# SteppyMk2.net
KiCad netlist of a schematic drawn in EAGLE
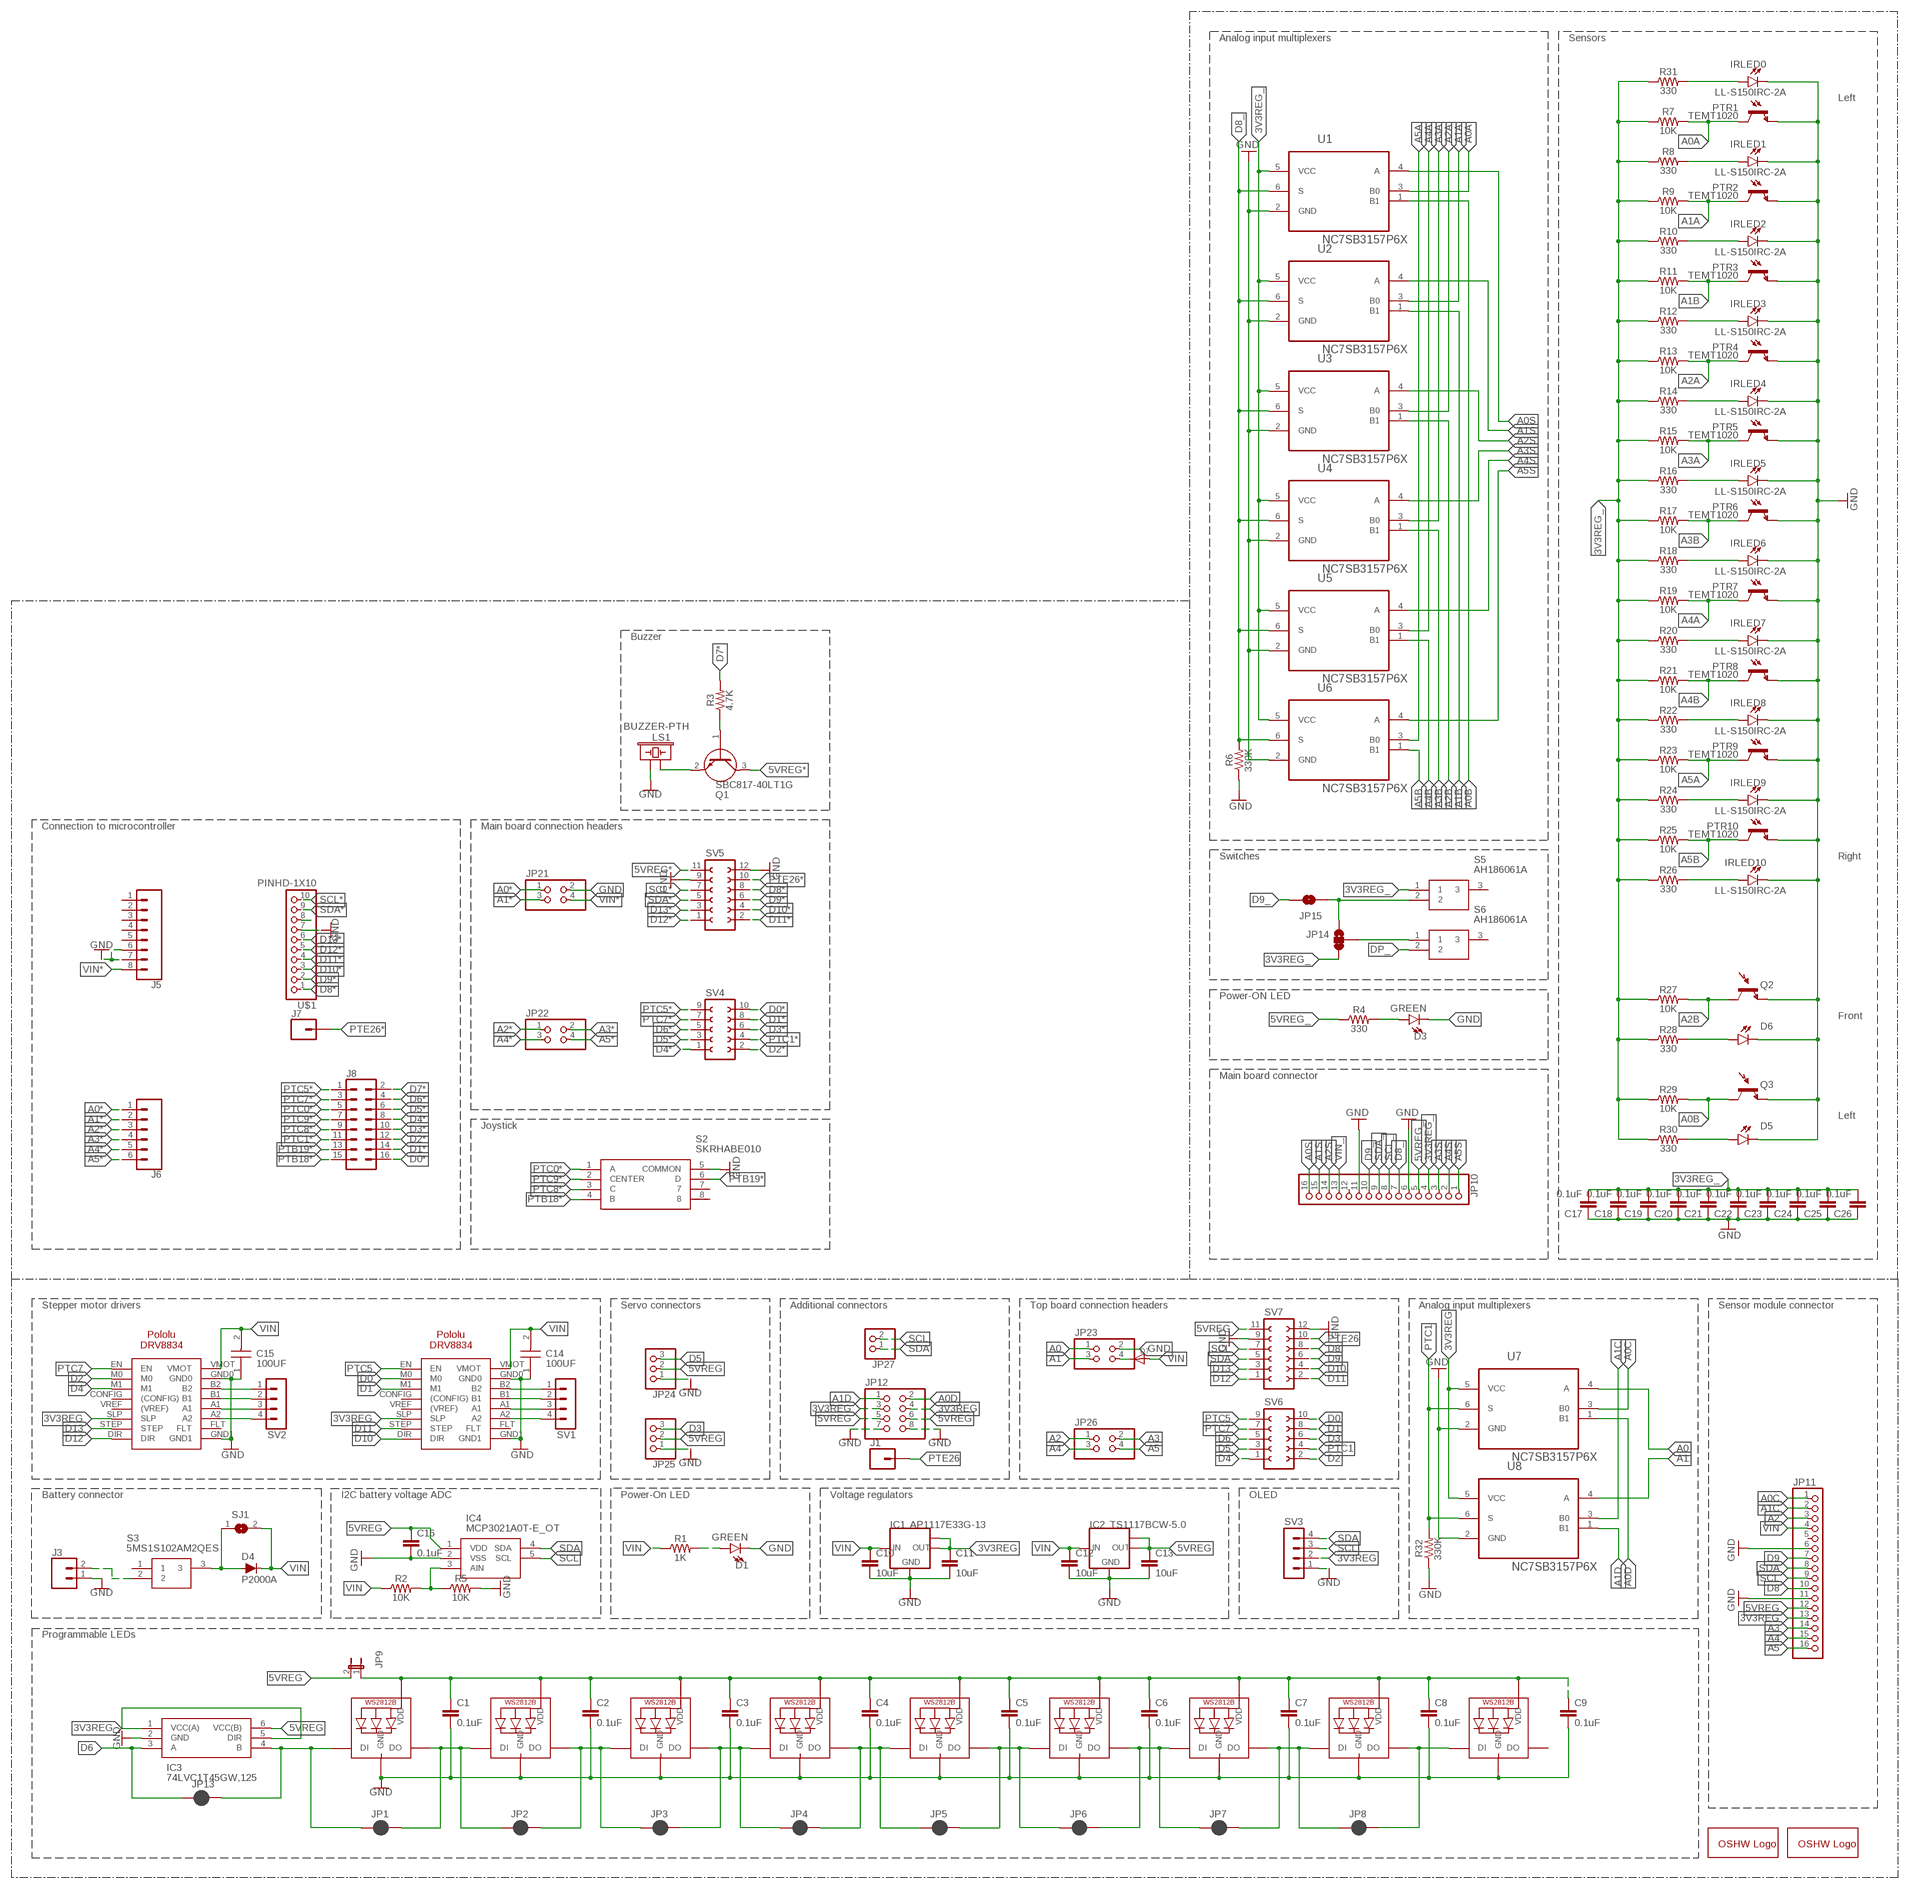
[diagram p0: schematic, sheet 1]

(export (version "E")
  (design (tool "Eeschema 10.0.6"))
  (components
    (comp (ref "C1")
      (value "0.1uF")
      (footprint "eagle-import:0603")
      (libsource (lib "eagle-import") (part "0.1UF-0603-25V-5%"))
    )
    (comp (ref "C2")
      (value "0.1uF")
      (footprint "eagle-import:0603")
      (libsource (lib "eagle-import") (part "0.1UF-0603-25V-5%"))
    )
    (comp (ref "C3")
      (value "0.1uF")
      (footprint "eagle-import:0603")
      (libsource (lib "eagle-import") (part "0.1UF-0603-25V-5%"))
    )
    (comp (ref "C4")
      (value "0.1uF")
      (footprint "eagle-import:0603")
      (libsource (lib "eagle-import") (part "0.1UF-0603-25V-5%"))
    )
    (comp (ref "C5")
      (value "0.1uF")
      (footprint "eagle-import:0603")
      (libsource (lib "eagle-import") (part "0.1UF-0603-25V-5%"))
    )
    (comp (ref "C6")
      (value "0.1uF")
      (footprint "eagle-import:0603")
      (libsource (lib "eagle-import") (part "0.1UF-0603-25V-5%"))
    )
    (comp (ref "C7")
      (value "0.1uF")
      (footprint "eagle-import:0603")
      (libsource (lib "eagle-import") (part "0.1UF-0603-25V-5%"))
    )
    (comp (ref "C8")
      (value "0.1uF")
      (footprint "eagle-import:0603")
      (libsource (lib "eagle-import") (part "0.1UF-0603-25V-5%"))
    )
    (comp (ref "C9")
      (value "0.1uF")
      (footprint "eagle-import:0603")
      (libsource (lib "eagle-import") (part "0.1UF-0603-25V-5%"))
    )
    (comp (ref "C10")
      (value "10uF")
      (footprint "eagle-import:0805")
      (libsource (lib "eagle-import") (part "10UF-0805-10V-10%"))
    )
    (comp (ref "C11")
      (value "10uF")
      (footprint "eagle-import:0805")
      (libsource (lib "eagle-import") (part "10UF-0805-10V-10%"))
    )
    (comp (ref "C12")
      (value "10uF")
      (footprint "eagle-import:0805")
      (libsource (lib "eagle-import") (part "10UF-0805-10V-10%"))
    )
    (comp (ref "C13")
      (value "10uF")
      (footprint "eagle-import:0805")
      (libsource (lib "eagle-import") (part "10UF-0805-10V-10%"))
    )
    (comp (ref "C14")
      (value "100UF")
      (footprint "eagle-import:CAPM7058X610N")
      (fields
        (field (name "MANUFACTURER_PART_NUMBER") "EEEFK1C101P")
        (field (name "RS_PART_NUMBER") "5370433P")
      )
      (libsource (lib "eagle-import") (part "EEEFK1C101P"))
    )
    (comp (ref "C15")
      (value "100UF")
      (footprint "eagle-import:CAPM7058X610N")
      (fields
        (field (name "MANUFACTURER_PART_NUMBER") "EEEFK1C101P")
        (field (name "RS_PART_NUMBER") "5370433P")
      )
      (libsource (lib "eagle-import") (part "EEEFK1C101P"))
    )
    (comp (ref "C16")
      (value "0.1uF")
      (footprint "eagle-import:0603")
      (libsource (lib "eagle-import") (part "0.1UF-0603-25V-5%"))
    )
    (comp (ref "C17")
      (value "0.1uF")
      (footprint "eagle-import:0603")
      (libsource (lib "eagle-import") (part "0.1UF-0603-25V-5%"))
    )
    (comp (ref "C18")
      (value "0.1uF")
      (footprint "eagle-import:0603")
      (libsource (lib "eagle-import") (part "0.1UF-0603-25V-5%"))
    )
    (comp (ref "C19")
      (value "0.1uF")
      (footprint "eagle-import:0603")
      (libsource (lib "eagle-import") (part "0.1UF-0603-25V-5%"))
    )
    (comp (ref "C20")
      (value "0.1uF")
      (footprint "eagle-import:0603")
      (libsource (lib "eagle-import") (part "0.1UF-0603-25V-5%"))
    )
    (comp (ref "C21")
      (value "0.1uF")
      (footprint "eagle-import:0603")
      (libsource (lib "eagle-import") (part "0.1UF-0603-25V-5%"))
    )
    (comp (ref "C22")
      (value "0.1uF")
      (footprint "eagle-import:0603")
      (libsource (lib "eagle-import") (part "0.1UF-0603-25V-5%"))
    )
    (comp (ref "C23")
      (value "0.1uF")
      (footprint "eagle-import:0603")
      (libsource (lib "eagle-import") (part "0.1UF-0603-25V-5%"))
    )
    (comp (ref "C24")
      (value "0.1uF")
      (footprint "eagle-import:0603")
      (libsource (lib "eagle-import") (part "0.1UF-0603-25V-5%"))
    )
    (comp (ref "C25")
      (value "0.1uF")
      (footprint "eagle-import:0603")
      (libsource (lib "eagle-import") (part "0.1UF-0603-25V-5%"))
    )
    (comp (ref "C26")
      (value "0.1uF")
      (footprint "eagle-import:0603")
      (libsource (lib "eagle-import") (part "0.1UF-0603-25V-5%"))
    )
    (comp (ref "CONLEFT")
      (value "POLOLU-DRV8825")
      (footprint "eagle-import:POLOLU-DRV8825")
      (libsource (lib "eagle-import") (part "POLOLU-DRV8825"))
    )
    (comp (ref "D1")
      (value "GREEN")
      (footprint "eagle-import:LED-1206")
      (libsource (lib "eagle-import") (part "LED-GREEN1206"))
    )
    (comp (ref "D3")
      (value "GREEN")
      (footprint "eagle-import:LED-1206")
      (libsource (lib "eagle-import") (part "LED-GREEN1206"))
    )
    (comp (ref "D4")
      (value "P2000A")
      (footprint "eagle-import:DIODE-1N4001")
      (libsource (lib "eagle-import") (part "DIODE-PTH"))
    )
    (comp (ref "D5")
      (value "LED-IRSIDE_EMITTER")
      (footprint "eagle-import:LTE-302")
      (libsource (lib "eagle-import") (part "LED-IRSIDE_EMITTER"))
    )
    (comp (ref "D6")
      (value "LED-IRSIDE_EMITTER")
      (footprint "eagle-import:LTE-302")
      (libsource (lib "eagle-import") (part "LED-IRSIDE_EMITTER"))
    )
    (comp (ref "D7")
      (value "DIODESMA")
      (footprint "eagle-import:SMADIODE")
      (libsource (lib "eagle-import") (part "DIODESMA"))
    )
    (comp (ref "GOLD_ORB_SM1")
      (value "OSHWLOGOLOGO8MM")
      (footprint "eagle-import:OSHW_8MM")
      (libsource (lib "eagle-import") (part "OSHWLOGOLOGO8MM"))
    )
    (comp (ref "GOLD_ORB_SM2")
      (value "OSHWLOGOLOGO5MM")
      (footprint "eagle-import:OSHW_5MM")
      (libsource (lib "eagle-import") (part "OSHWLOGOLOGO5MM"))
    )
    (comp (ref "IC1")
      (value "AP1117E33G-13")
      (footprint "eagle-import:SOT223")
      (libsource (lib "eagle-import") (part "LM1117IMPX-3.3"))
    )
    (comp (ref "IC2")
      (value "TS1117BCW-5.0")
      (footprint "eagle-import:SOT223")
      (libsource (lib "eagle-import") (part "LM1117IMPX-5.0"))
    )
    (comp (ref "IC3")
      (value "74LVC1T45GW,125")
      (footprint "eagle-import:SOT65P210X110-6N")
      (fields
        (field (name "MOUSER_PART_NUMBER") "771-74LVC1T45GW125")
        (field (name "RS_PART_NUMBER") "8168791P")
      )
      (libsource (lib "eagle-import") (part "74LVC1T45GW,125"))
    )
    (comp (ref "IC4")
      (value "MCP3021A0T-E_OT")
      (footprint "eagle-import:SOT95P280X145-5N")
      (fields
        (field (name "MANUFACTURER_PART_NUMBER") "MCP3021A0T-E/OT")
        (field (name "MOUSER_PART_NUMBER") "579-MCP3021A0T-E/OT")
      )
      (libsource (lib "eagle-import") (part "MCP3021A0T-E_OT"))
    )
    (comp (ref "IRLED0")
      (value "LL-S150IRC-2A")
      (footprint "eagle-import:LEDC3215X130N")
      (fields
        (field (name "MANUFACTURER_PART_NUMBER") "PT15-21C/TR8")
        (field (name "MOUSER_PART_NUMBER") "638-PT1521CTR8")
      )
      (libsource (lib "eagle-import") (part "PT15-21C_TR8"))
    )
    (comp (ref "IRLED1")
      (value "LL-S150IRC-2A")
      (footprint "eagle-import:LEDC3215X130N")
      (fields
        (field (name "MANUFACTURER_PART_NUMBER") "PT15-21C/TR8")
        (field (name "MOUSER_PART_NUMBER") "638-PT1521CTR8")
      )
      (libsource (lib "eagle-import") (part "PT15-21C_TR8"))
    )
    (comp (ref "IRLED2")
      (value "LL-S150IRC-2A")
      (footprint "eagle-import:LEDC3215X130N")
      (fields
        (field (name "MANUFACTURER_PART_NUMBER") "PT15-21C/TR8")
        (field (name "MOUSER_PART_NUMBER") "638-PT1521CTR8")
      )
      (libsource (lib "eagle-import") (part "PT15-21C_TR8"))
    )
    (comp (ref "IRLED3")
      (value "LL-S150IRC-2A")
      (footprint "eagle-import:LEDC3215X130N")
      (fields
        (field (name "MANUFACTURER_PART_NUMBER") "PT15-21C/TR8")
        (field (name "MOUSER_PART_NUMBER") "638-PT1521CTR8")
      )
      (libsource (lib "eagle-import") (part "PT15-21C_TR8"))
    )
    (comp (ref "IRLED4")
      (value "LL-S150IRC-2A")
      (footprint "eagle-import:LEDC3215X130N")
      (fields
        (field (name "MANUFACTURER_PART_NUMBER") "PT15-21C/TR8")
        (field (name "MOUSER_PART_NUMBER") "638-PT1521CTR8")
      )
      (libsource (lib "eagle-import") (part "PT15-21C_TR8"))
    )
    (comp (ref "IRLED5")
      (value "LL-S150IRC-2A")
      (footprint "eagle-import:LEDC3215X130N")
      (fields
        (field (name "MANUFACTURER_PART_NUMBER") "PT15-21C/TR8")
        (field (name "MOUSER_PART_NUMBER") "638-PT1521CTR8")
      )
      (libsource (lib "eagle-import") (part "PT15-21C_TR8"))
    )
    (comp (ref "IRLED6")
      (value "LL-S150IRC-2A")
      (footprint "eagle-import:LEDC3215X130N")
      (fields
        (field (name "MANUFACTURER_PART_NUMBER") "PT15-21C/TR8")
        (field (name "MOUSER_PART_NUMBER") "638-PT1521CTR8")
      )
      (libsource (lib "eagle-import") (part "PT15-21C_TR8"))
    )
    (comp (ref "IRLED7")
      (value "LL-S150IRC-2A")
      (footprint "eagle-import:LEDC3215X130N")
      (fields
        (field (name "MANUFACTURER_PART_NUMBER") "PT15-21C/TR8")
        (field (name "MOUSER_PART_NUMBER") "638-PT1521CTR8")
      )
      (libsource (lib "eagle-import") (part "PT15-21C_TR8"))
    )
    (comp (ref "IRLED8")
      (value "LL-S150IRC-2A")
      (footprint "eagle-import:LEDC3215X130N")
      (fields
        (field (name "MANUFACTURER_PART_NUMBER") "PT15-21C/TR8")
        (field (name "MOUSER_PART_NUMBER") "638-PT1521CTR8")
      )
      (libsource (lib "eagle-import") (part "PT15-21C_TR8"))
    )
    (comp (ref "IRLED9")
      (value "LL-S150IRC-2A")
      (footprint "eagle-import:LEDC3215X130N")
      (fields
        (field (name "MANUFACTURER_PART_NUMBER") "PT15-21C/TR8")
        (field (name "MOUSER_PART_NUMBER") "638-PT1521CTR8")
      )
      (libsource (lib "eagle-import") (part "PT15-21C_TR8"))
    )
    (comp (ref "IRLED10")
      (value "LL-S150IRC-2A")
      (footprint "eagle-import:LEDC3215X130N")
      (fields
        (field (name "MANUFACTURER_PART_NUMBER") "PT15-21C/TR8")
        (field (name "MOUSER_PART_NUMBER") "638-PT1521CTR8")
      )
      (libsource (lib "eagle-import") (part "PT15-21C_TR8"))
    )
    (comp (ref "J1")
      (value "CONN_01")
      (footprint "eagle-import:1X01")
      (libsource (lib "eagle-import") (part "CONN_01"))
    )
    (comp (ref "J3")
      (value "CONN_02")
      (footprint "eagle-import:1X02")
      (libsource (lib "eagle-import") (part "CONN_02"))
    )
    (comp (ref "J5")
      (value "CONN_08\"")
      (footprint "eagle-import:1X08")
      (libsource (lib "eagle-import") (part "CONN_08{dblquote}"))
    )
    (comp (ref "J6")
      (value "CONN_06SILK_FEMALE_PTH")
      (footprint "eagle-import:1X06")
      (libsource (lib "eagle-import") (part "CONN_06SILK_FEMALE_PTH"))
    )
    (comp (ref "J7")
      (value "CONN_01")
      (footprint "eagle-import:1X01")
      (libsource (lib "eagle-import") (part "CONN_01"))
    )
    (comp (ref "J8")
      (value "CONN_08X2_HEADER")
      (footprint "eagle-import:2X8")
      (libsource (lib "eagle-import") (part "CONN_08X2_HEADER"))
    )
    (comp (ref "JP1")
      (value "JUMPER-SMT_2_NC_PASTE_SILK")
      (footprint "eagle-import:SMT-JUMPER_2_NC_PASTE_SILK")
      (libsource (lib "eagle-import") (part "JUMPER-SMT_2_NC_PASTE_SILK"))
    )
    (comp (ref "JP2")
      (value "JUMPER-SMT_2_NC_PASTE_SILK")
      (footprint "eagle-import:SMT-JUMPER_2_NC_PASTE_SILK")
      (libsource (lib "eagle-import") (part "JUMPER-SMT_2_NC_PASTE_SILK"))
    )
    (comp (ref "JP3")
      (value "JUMPER-SMT_2_NC_PASTE_SILK")
      (footprint "eagle-import:SMT-JUMPER_2_NC_PASTE_SILK")
      (libsource (lib "eagle-import") (part "JUMPER-SMT_2_NC_PASTE_SILK"))
    )
    (comp (ref "JP4")
      (value "JUMPER-SMT_2_NC_PASTE_SILK")
      (footprint "eagle-import:SMT-JUMPER_2_NC_PASTE_SILK")
      (libsource (lib "eagle-import") (part "JUMPER-SMT_2_NC_PASTE_SILK"))
    )
    (comp (ref "JP5")
      (value "JUMPER-SMT_2_NC_PASTE_SILK")
      (footprint "eagle-import:SMT-JUMPER_2_NC_PASTE_SILK")
      (libsource (lib "eagle-import") (part "JUMPER-SMT_2_NC_PASTE_SILK"))
    )
    (comp (ref "JP6")
      (value "JUMPER-SMT_2_NC_PASTE_SILK")
      (footprint "eagle-import:SMT-JUMPER_2_NC_PASTE_SILK")
      (libsource (lib "eagle-import") (part "JUMPER-SMT_2_NC_PASTE_SILK"))
    )
    (comp (ref "JP7")
      (value "JUMPER-SMT_2_NC_PASTE_SILK")
      (footprint "eagle-import:SMT-JUMPER_2_NC_PASTE_SILK")
      (libsource (lib "eagle-import") (part "JUMPER-SMT_2_NC_PASTE_SILK"))
    )
    (comp (ref "JP8")
      (value "JUMPER-SMT_2_NC_PASTE_SILK")
      (footprint "eagle-import:SMT-JUMPER_2_NC_PASTE_SILK")
      (libsource (lib "eagle-import") (part "JUMPER-SMT_2_NC_PASTE_SILK"))
    )
    (comp (ref "JP9")
      (value "JP1E")
      (footprint "eagle-import:JP1")
      (libsource (lib "eagle-import") (part "JP1E"))
    )
    (comp (ref "JP10")
      (value "PINHD-1X16/90")
      (footprint "eagle-import:1X16_90")
      (libsource (lib "eagle-import") (part "PINHD-1X16/90"))
    )
    (comp (ref "JP11")
      (value "PINHD-1X16")
      (footprint "eagle-import:1X16")
      (libsource (lib "eagle-import") (part "PINHD-1X16"))
    )
    (comp (ref "JP12")
      (value "PINHD-2X4")
      (footprint "eagle-import:2X04")
      (libsource (lib "eagle-import") (part "PINHD-2X4"))
    )
    (comp (ref "JP13")
      (value "JUMPER-SMT_2_NC_PASTE_SILK")
      (footprint "eagle-import:SMT-JUMPER_2_NC_PASTE_SILK")
      (libsource (lib "eagle-import") (part "JUMPER-SMT_2_NC_PASTE_SILK"))
    )
    (comp (ref "JP14")
      (value "JUMPER-SMT_3_1-NC_TRACE_SILK")
      (footprint "eagle-import:SMT-JUMPER_3_1-NC_TRACE_SILK")
      (libsource (lib "eagle-import") (part "JUMPER-SMT_3_1-NC_TRACE_SILK"))
    )
    (comp (ref "JP15")
      (value "JUMPER-SMT_2_NC_TRACE_SILK")
      (footprint "eagle-import:SMT-JUMPER_2_NC_TRACE_SILK")
      (libsource (lib "eagle-import") (part "JUMPER-SMT_2_NC_TRACE_SILK"))
    )
    (comp (ref "JP21")
      (value "PINHD-2X2")
      (footprint "eagle-import:2X02")
      (libsource (lib "eagle-import") (part "PINHD-2X2"))
    )
    (comp (ref "JP22")
      (value "PINHD-2X2")
      (footprint "eagle-import:2X02")
      (libsource (lib "eagle-import") (part "PINHD-2X2"))
    )
    (comp (ref "JP23")
      (value "PINHD-2X2")
      (footprint "eagle-import:2X02")
      (libsource (lib "eagle-import") (part "PINHD-2X2"))
    )
    (comp (ref "JP24")
      (value "PINHD-1X3")
      (footprint "eagle-import:1X03")
      (libsource (lib "eagle-import") (part "PINHD-1X3"))
    )
    (comp (ref "JP25")
      (value "PINHD-1X3")
      (footprint "eagle-import:1X03")
      (libsource (lib "eagle-import") (part "PINHD-1X3"))
    )
    (comp (ref "JP26")
      (value "PINHD-2X2")
      (footprint "eagle-import:2X02")
      (libsource (lib "eagle-import") (part "PINHD-2X2"))
    )
    (comp (ref "JP27")
      (value "PINHD-1X2")
      (footprint "eagle-import:1X02")
      (libsource (lib "eagle-import") (part "PINHD-1X2"))
    )
    (comp (ref "LED1")
      (value "WS2812B3535")
      (footprint "eagle-import:LED3535")
      (libsource (lib "eagle-import") (part "WS2812B3535"))
    )
    (comp (ref "LED2")
      (value "WS2812B3535")
      (footprint "eagle-import:LED3535")
      (libsource (lib "eagle-import") (part "WS2812B3535"))
    )
    (comp (ref "LED3")
      (value "WS2812B3535")
      (footprint "eagle-import:LED3535")
      (libsource (lib "eagle-import") (part "WS2812B3535"))
    )
    (comp (ref "LED4")
      (value "WS2812B3535")
      (footprint "eagle-import:LED3535")
      (libsource (lib "eagle-import") (part "WS2812B3535"))
    )
    (comp (ref "LED5")
      (value "WS2812B3535")
      (footprint "eagle-import:LED3535")
      (libsource (lib "eagle-import") (part "WS2812B3535"))
    )
    (comp (ref "LED6")
      (value "WS2812B3535")
      (footprint "eagle-import:LED3535")
      (libsource (lib "eagle-import") (part "WS2812B3535"))
    )
    (comp (ref "LED7")
      (value "WS2812B3535")
      (footprint "eagle-import:LED3535")
      (libsource (lib "eagle-import") (part "WS2812B3535"))
    )
    (comp (ref "LED8")
      (value "WS2812B3535")
      (footprint "eagle-import:LED3535")
      (libsource (lib "eagle-import") (part "WS2812B3535"))
    )
    (comp (ref "LED9")
      (value "WS2812B3535")
      (footprint "eagle-import:LED3535")
      (libsource (lib "eagle-import") (part "WS2812B3535"))
    )
    (comp (ref "LS1")
      (value "BUZZER-PTH")
      (footprint "eagle-import:BUZZER-12MM")
      (libsource (lib "eagle-import") (part "BUZZER-PTH"))
    )
    (comp (ref "PTR1")
      (value "TEMT1020")
      (footprint "eagle-import:TEMT1020")
      (fields
        (field (name "MANUFACTURER_PART_NUMBER") "TEMD1020")
        (field (name "MOUSER_PART_NUMBER") "782-TEMD1020")
        (field (name "RS_PART_NUMBER") "1808105P")
      )
      (libsource (lib "eagle-import") (part "TEMT1020"))
    )
    (comp (ref "PTR2")
      (value "TEMT1020")
      (footprint "eagle-import:TEMT1020")
      (fields
        (field (name "MANUFACTURER_PART_NUMBER") "TEMD1020")
        (field (name "MOUSER_PART_NUMBER") "782-TEMD1020")
        (field (name "RS_PART_NUMBER") "1808105P")
      )
      (libsource (lib "eagle-import") (part "TEMT1020"))
    )
    (comp (ref "PTR3")
      (value "TEMT1020")
      (footprint "eagle-import:TEMT1020")
      (fields
        (field (name "MANUFACTURER_PART_NUMBER") "TEMD1020")
        (field (name "MOUSER_PART_NUMBER") "782-TEMD1020")
        (field (name "RS_PART_NUMBER") "1808105P")
      )
      (libsource (lib "eagle-import") (part "TEMT1020"))
    )
    (comp (ref "PTR4")
      (value "TEMT1020")
      (footprint "eagle-import:TEMT1020")
      (fields
        (field (name "MANUFACTURER_PART_NUMBER") "TEMD1020")
        (field (name "MOUSER_PART_NUMBER") "782-TEMD1020")
        (field (name "RS_PART_NUMBER") "1808105P")
      )
      (libsource (lib "eagle-import") (part "TEMT1020"))
    )
    (comp (ref "PTR5")
      (value "TEMT1020")
      (footprint "eagle-import:TEMT1020")
      (fields
        (field (name "MANUFACTURER_PART_NUMBER") "TEMD1020")
        (field (name "MOUSER_PART_NUMBER") "782-TEMD1020")
        (field (name "RS_PART_NUMBER") "1808105P")
      )
      (libsource (lib "eagle-import") (part "TEMT1020"))
    )
    (comp (ref "PTR6")
      (value "TEMT1020")
      (footprint "eagle-import:TEMT1020")
      (fields
        (field (name "MANUFACTURER_PART_NUMBER") "TEMD1020")
        (field (name "MOUSER_PART_NUMBER") "782-TEMD1020")
        (field (name "RS_PART_NUMBER") "1808105P")
      )
      (libsource (lib "eagle-import") (part "TEMT1020"))
    )
    (comp (ref "PTR7")
      (value "TEMT1020")
      (footprint "eagle-import:TEMT1020")
      (fields
        (field (name "MANUFACTURER_PART_NUMBER") "TEMD1020")
        (field (name "MOUSER_PART_NUMBER") "782-TEMD1020")
        (field (name "RS_PART_NUMBER") "1808105P")
      )
      (libsource (lib "eagle-import") (part "TEMT1020"))
    )
    (comp (ref "PTR8")
      (value "TEMT1020")
      (footprint "eagle-import:TEMT1020")
      (fields
        (field (name "MANUFACTURER_PART_NUMBER") "TEMD1020")
        (field (name "MOUSER_PART_NUMBER") "782-TEMD1020")
        (field (name "RS_PART_NUMBER") "1808105P")
      )
      (libsource (lib "eagle-import") (part "TEMT1020"))
    )
    (comp (ref "PTR9")
      (value "TEMT1020")
      (footprint "eagle-import:TEMT1020")
      (fields
        (field (name "MANUFACTURER_PART_NUMBER") "TEMD1020")
        (field (name "MOUSER_PART_NUMBER") "782-TEMD1020")
        (field (name "RS_PART_NUMBER") "1808105P")
      )
      (libsource (lib "eagle-import") (part "TEMT1020"))
    )
    (comp (ref "PTR10")
      (value "TEMT1020")
      (footprint "eagle-import:TEMT1020")
      (fields
        (field (name "MANUFACTURER_PART_NUMBER") "TEMD1020")
        (field (name "MOUSER_PART_NUMBER") "782-TEMD1020")
        (field (name "RS_PART_NUMBER") "1808105P")
      )
      (libsource (lib "eagle-import") (part "TEMT1020"))
    )
    (comp (ref "Q1")
      (value "SBC817-40LT1G")
      (footprint "eagle-import:SOT96P237X111-3N")
      (fields
        (field (name "MOUSER_PART_NUMBER") "863-SBC817-40LT1G")
        (field (name "RS_PART_NUMBER") "1631159")
      )
      (libsource (lib "eagle-import") (part "SBC817-40LT1G"))
    )
    (comp (ref "Q2")
      (value "LTR-301")
      (footprint "eagle-import:LTR-301")
      (libsource (lib "eagle-import") (part "LTR-301"))
    )
    (comp (ref "Q3")
      (value "LTR-301")
      (footprint "eagle-import:LTR-301")
      (libsource (lib "eagle-import") (part "LTR-301"))
    )
    (comp (ref "R1")
      (value "1K")
      (footprint "eagle-import:0805")
      (libsource (lib "eagle-import") (part "RESISTOR0805"))
    )
    (comp (ref "R2")
      (value "10K")
      (footprint "eagle-import:0805")
      (libsource (lib "eagle-import") (part "RESISTOR0805"))
    )
    (comp (ref "R3")
      (value "4.7K")
      (footprint "eagle-import:0805")
      (libsource (lib "eagle-import") (part "RESISTOR0805"))
    )
    (comp (ref "R4")
      (value "330")
      (footprint "eagle-import:0805")
      (libsource (lib "eagle-import") (part "RESISTOR0805"))
    )
    (comp (ref "R5")
      (value "10K")
      (footprint "eagle-import:0805")
      (libsource (lib "eagle-import") (part "RESISTOR0805"))
    )
    (comp (ref "R6")
      (value "330K")
      (footprint "eagle-import:0805")
      (libsource (lib "eagle-import") (part "RESISTOR0805"))
    )
    (comp (ref "R7")
      (value "10K")
      (footprint "eagle-import:0805")
      (libsource (lib "eagle-import") (part "RESISTOR0805"))
    )
    (comp (ref "R8")
      (value "330")
      (footprint "eagle-import:0805")
      (libsource (lib "eagle-import") (part "RESISTOR0805"))
    )
    (comp (ref "R9")
      (value "10K")
      (footprint "eagle-import:0805")
      (libsource (lib "eagle-import") (part "RESISTOR0805"))
    )
    (comp (ref "R10")
      (value "330")
      (footprint "eagle-import:0805")
      (libsource (lib "eagle-import") (part "RESISTOR0805"))
    )
    (comp (ref "R11")
      (value "10K")
      (footprint "eagle-import:0805")
      (libsource (lib "eagle-import") (part "RESISTOR0805"))
    )
    (comp (ref "R12")
      (value "330")
      (footprint "eagle-import:0805")
      (libsource (lib "eagle-import") (part "RESISTOR0805"))
    )
    (comp (ref "R13")
      (value "10K")
      (footprint "eagle-import:0805")
      (libsource (lib "eagle-import") (part "RESISTOR0805"))
    )
    (comp (ref "R14")
      (value "330")
      (footprint "eagle-import:0805")
      (libsource (lib "eagle-import") (part "RESISTOR0805"))
    )
    (comp (ref "R15")
      (value "10K")
      (footprint "eagle-import:0805")
      (libsource (lib "eagle-import") (part "RESISTOR0805"))
    )
    (comp (ref "R16")
      (value "330")
      (footprint "eagle-import:0805")
      (libsource (lib "eagle-import") (part "RESISTOR0805"))
    )
    (comp (ref "R17")
      (value "10K")
      (footprint "eagle-import:0805")
      (libsource (lib "eagle-import") (part "RESISTOR0805"))
    )
    (comp (ref "R18")
      (value "330")
      (footprint "eagle-import:0805")
      (libsource (lib "eagle-import") (part "RESISTOR0805"))
    )
    (comp (ref "R19")
      (value "10K")
      (footprint "eagle-import:0805")
      (libsource (lib "eagle-import") (part "RESISTOR0805"))
    )
    (comp (ref "R20")
      (value "330")
      (footprint "eagle-import:0805")
      (libsource (lib "eagle-import") (part "RESISTOR0805"))
    )
    (comp (ref "R21")
      (value "10K")
      (footprint "eagle-import:0805")
      (libsource (lib "eagle-import") (part "RESISTOR0805"))
    )
    (comp (ref "R22")
      (value "330")
      (footprint "eagle-import:0805")
      (libsource (lib "eagle-import") (part "RESISTOR0805"))
    )
    (comp (ref "R23")
      (value "10K")
      (footprint "eagle-import:0805")
      (libsource (lib "eagle-import") (part "RESISTOR0805"))
    )
    (comp (ref "R24")
      (value "330")
      (footprint "eagle-import:0805")
      (libsource (lib "eagle-import") (part "RESISTOR0805"))
    )
    (comp (ref "R25")
      (value "10K")
      (footprint "eagle-import:0805")
      (libsource (lib "eagle-import") (part "RESISTOR0805"))
    )
    (comp (ref "R26")
      (value "330")
      (footprint "eagle-import:0805")
      (libsource (lib "eagle-import") (part "RESISTOR0805"))
    )
    (comp (ref "R27")
      (value "10K")
      (footprint "eagle-import:0805")
      (libsource (lib "eagle-import") (part "RESISTOR0805"))
    )
    (comp (ref "R28")
      (value "330")
      (footprint "eagle-import:0805")
      (libsource (lib "eagle-import") (part "RESISTOR0805"))
    )
    (comp (ref "R29")
      (value "10K")
      (footprint "eagle-import:0805")
      (libsource (lib "eagle-import") (part "RESISTOR0805"))
    )
    (comp (ref "R30")
      (value "330")
      (footprint "eagle-import:0805")
      (libsource (lib "eagle-import") (part "RESISTOR0805"))
    )
    (comp (ref "R31")
      (value "330")
      (footprint "eagle-import:0805")
      (libsource (lib "eagle-import") (part "RESISTOR0805"))
    )
    (comp (ref "R32")
      (value "330K")
      (footprint "eagle-import:0805")
      (libsource (lib "eagle-import") (part "RESISTOR0805"))
    )
    (comp (ref "S2")
      (value "SKRHABE010")
      (footprint "eagle-import:SKRHABE010")
      (fields (field (name "MOUSER_PART_NUMBER") "688-SKRHAB"))
      (libsource (lib "eagle-import") (part "SKRHABE010"))
    )
    (comp (ref "S3")
      (value "5MS1S102AM2QES")
      (footprint "eagle-import:5MS1S102AM2QES")
      (fields (field (name "RS_PART_NUMBER") "7347292"))
      (libsource (lib "eagle-import") (part "5MS1S102AM2QES"))
    )
    (comp (ref "S5")
      (value "AH186061A")
      (footprint "eagle-import:AH186061A")
      (libsource (lib "eagle-import") (part "AH186061A"))
    )
    (comp (ref "S6")
      (value "AH186061A")
      (footprint "eagle-import:AH186061A")
      (libsource (lib "eagle-import") (part "AH186061A"))
    )
    (comp (ref "SJ1")
      (value "SJW")
      (footprint "eagle-import:SJW")
      (libsource (lib "eagle-import") (part "SJW"))
    )
    (comp (ref "SV1")
      (value "MA04-1")
      (footprint "eagle-import:MA04-1")
      (libsource (lib "eagle-import") (part "MA04-1"))
    )
    (comp (ref "SV2")
      (value "MA04-1")
      (footprint "eagle-import:MA04-1")
      (libsource (lib "eagle-import") (part "MA04-1"))
    )
    (comp (ref "SV3")
      (value "MA04-1")
      (footprint "eagle-import:MA04-1")
      (libsource (lib "eagle-import") (part "MA04-1"))
    )
    (comp (ref "SV4")
      (value "FE05-2")
      (footprint "eagle-import:FE05-2")
      (libsource (lib "eagle-import") (part "FE05-2"))
    )
    (comp (ref "SV5")
      (value "FE06-2")
      (footprint "eagle-import:FE06-2")
      (libsource (lib "eagle-import") (part "FE06-2"))
    )
    (comp (ref "SV6")
      (value "FE05-2")
      (footprint "eagle-import:FE05-2")
      (libsource (lib "eagle-import") (part "FE05-2"))
    )
    (comp (ref "SV7")
      (value "FE06-2")
      (footprint "eagle-import:FE06-2")
      (libsource (lib "eagle-import") (part "FE06-2"))
    )
    (comp (ref "U$1")
      (value "PINHD-1X10")
      (footprint "eagle-import:1X10-BIG")
      (libsource (lib "eagle-import") (part "PINHD-1X10"))
    )
    (comp (ref "U$2")
      (value "POLOLU-DRV8825")
      (footprint "eagle-import:POLOLU-DRV8825")
      (libsource (lib "eagle-import") (part "POLOLU-DRV8825"))
    )
    (comp (ref "U1")
      (value "NC7SB3157P6X")
      (footprint "eagle-import:SOT65P210X110-6N")
      (fields (field (name "MF") "ON Semiconductor"))
      (libsource (lib "eagle-import") (part "NC7SB3157P6X"))
    )
    (comp (ref "U2")
      (value "NC7SB3157P6X")
      (footprint "eagle-import:SOT65P210X110-6N")
      (fields (field (name "MF") "ON Semiconductor"))
      (libsource (lib "eagle-import") (part "NC7SB3157P6X"))
    )
    (comp (ref "U3")
      (value "NC7SB3157P6X")
      (footprint "eagle-import:SOT65P210X110-6N")
      (fields (field (name "MF") "ON Semiconductor"))
      (libsource (lib "eagle-import") (part "NC7SB3157P6X"))
    )
    (comp (ref "U4")
      (value "NC7SB3157P6X")
      (footprint "eagle-import:SOT65P210X110-6N")
      (fields (field (name "MF") "ON Semiconductor"))
      (libsource (lib "eagle-import") (part "NC7SB3157P6X"))
    )
    (comp (ref "U5")
      (value "NC7SB3157P6X")
      (footprint "eagle-import:SOT65P210X110-6N")
      (fields (field (name "MF") "ON Semiconductor"))
      (libsource (lib "eagle-import") (part "NC7SB3157P6X"))
    )
    (comp (ref "U6")
      (value "NC7SB3157P6X")
      (footprint "eagle-import:SOT65P210X110-6N")
      (fields (field (name "MF") "ON Semiconductor"))
      (libsource (lib "eagle-import") (part "NC7SB3157P6X"))
    )
    (comp (ref "U7")
      (value "NC7SB3157P6X")
      (footprint "eagle-import:SOT65P210X110-6N")
      (fields (field (name "MF") "ON Semiconductor"))
      (libsource (lib "eagle-import") (part "NC7SB3157P6X"))
    )
    (comp (ref "U8")
      (value "NC7SB3157P6X")
      (footprint "eagle-import:SOT65P210X110-6N")
      (fields (field (name "MF") "ON Semiconductor"))
      (libsource (lib "eagle-import") (part "NC7SB3157P6X"))
    )
  )
  (nets
    (net (code "1") (name "3V3REG") (class "Default")
      (node (ref "C11") (pin "1") (pinfunction "1_1") (pintype "passive"))
      (node (ref "CONLEFT") (pin "SLP") (pinfunction "SLP_SLP") (pintype "bidirectional"))
      (node (ref "IC1") (pin "2") (pinfunction "OUT_2") (pintype "passive"))
      (node (ref "IC1") (pin "TAB") (pinfunction "OUT1_TAB") (pintype "passive"))
      (node (ref "IC3") (pin "1") (pinfunction "VCC(A)_1") (pintype "power_in"))
      (node (ref "IC3") (pin "5") (pinfunction "DIR_5") (pintype "input"))
      (node (ref "JP11") (pin "13") (pinfunction "13_13") (pintype "passive"))
      (node (ref "JP12") (pin "3") (pinfunction "3_3") (pintype "passive"))
      (node (ref "JP12") (pin "4") (pinfunction "4_4") (pintype "passive"))
      (node (ref "SV3") (pin "2") (pinfunction "2_2") (pintype "passive"))
      (node (ref "U$2") (pin "SLP") (pinfunction "SLP_SLP") (pintype "bidirectional"))
      (node (ref "U7") (pin "5") (pinfunction "VCC_5") (pintype "power_in"))
      (node (ref "U8") (pin "5") (pinfunction "VCC_5") (pintype "power_in"))
    )
    (net (code "2") (name "3V3REG_") (class "Default")
      (node (ref "C17") (pin "2") (pinfunction "2_2") (pintype "passive"))
      (node (ref "C18") (pin "2") (pinfunction "2_2") (pintype "passive"))
      (node (ref "C19") (pin "2") (pinfunction "2_2") (pintype "passive"))
      (node (ref "C20") (pin "2") (pinfunction "2_2") (pintype "passive"))
      (node (ref "C21") (pin "2") (pinfunction "2_2") (pintype "passive"))
      (node (ref "C22") (pin "2") (pinfunction "2_2") (pintype "passive"))
      (node (ref "C23") (pin "2") (pinfunction "2_2") (pintype "passive"))
      (node (ref "C24") (pin "2") (pinfunction "2_2") (pintype "passive"))
      (node (ref "C25") (pin "2") (pinfunction "2_2") (pintype "passive"))
      (node (ref "C26") (pin "2") (pinfunction "2_2") (pintype "passive"))
      (node (ref "JP10") (pin "4") (pinfunction "4_4") (pintype "passive"))
      (node (ref "JP14") (pin "3") (pinfunction "3_3") (pintype "passive"))
      (node (ref "R10") (pin "1") (pinfunction "1_1") (pintype "passive"))
      (node (ref "R11") (pin "1") (pinfunction "1_1") (pintype "passive"))
      (node (ref "R12") (pin "1") (pinfunction "1_1") (pintype "passive"))
      (node (ref "R13") (pin "1") (pinfunction "1_1") (pintype "passive"))
      (node (ref "R14") (pin "1") (pinfunction "1_1") (pintype "passive"))
      (node (ref "R15") (pin "1") (pinfunction "1_1") (pintype "passive"))
      (node (ref "R16") (pin "1") (pinfunction "1_1") (pintype "passive"))
      (node (ref "R17") (pin "1") (pinfunction "1_1") (pintype "passive"))
      (node (ref "R18") (pin "1") (pinfunction "1_1") (pintype "passive"))
      (node (ref "R19") (pin "1") (pinfunction "1_1") (pintype "passive"))
      (node (ref "R20") (pin "1") (pinfunction "1_1") (pintype "passive"))
      (node (ref "R21") (pin "1") (pinfunction "1_1") (pintype "passive"))
      (node (ref "R22") (pin "1") (pinfunction "1_1") (pintype "passive"))
      (node (ref "R23") (pin "1") (pinfunction "1_1") (pintype "passive"))
      (node (ref "R24") (pin "1") (pinfunction "1_1") (pintype "passive"))
      (node (ref "R25") (pin "1") (pinfunction "1_1") (pintype "passive"))
      (node (ref "R26") (pin "1") (pinfunction "1_1") (pintype "passive"))
      (node (ref "R27") (pin "1") (pinfunction "1_1") (pintype "passive"))
      (node (ref "R28") (pin "1") (pinfunction "1_1") (pintype "passive"))
      (node (ref "R29") (pin "1") (pinfunction "1_1") (pintype "passive"))
      (node (ref "R30") (pin "1") (pinfunction "1_1") (pintype "passive"))
      (node (ref "R31") (pin "1") (pinfunction "1_1") (pintype "passive"))
      (node (ref "R7") (pin "1") (pinfunction "1_1") (pintype "passive"))
      (node (ref "R8") (pin "1") (pinfunction "1_1") (pintype "passive"))
      (node (ref "R9") (pin "1") (pinfunction "1_1") (pintype "passive"))
      (node (ref "S5") (pin "1") (pinfunction "1_1") (pintype "bidirectional"))
      (node (ref "U1") (pin "5") (pinfunction "VCC_5") (pintype "power_in"))
      (node (ref "U2") (pin "5") (pinfunction "VCC_5") (pintype "power_in"))
      (node (ref "U3") (pin "5") (pinfunction "VCC_5") (pintype "power_in"))
      (node (ref "U4") (pin "5") (pinfunction "VCC_5") (pintype "power_in"))
      (node (ref "U5") (pin "5") (pinfunction "VCC_5") (pintype "power_in"))
      (node (ref "U6") (pin "5") (pinfunction "VCC_5") (pintype "power_in"))
    )
    (net (code "3") (name "5VREG") (class "Default")
      (node (ref "C13") (pin "1") (pinfunction "1_1") (pintype "passive"))
      (node (ref "C16") (pin "1") (pinfunction "1_1") (pintype "passive"))
      (node (ref "IC2") (pin "2") (pinfunction "OUT_2") (pintype "passive"))
      (node (ref "IC2") (pin "TAB") (pinfunction "OUT1_TAB") (pintype "passive"))
      (node (ref "IC3") (pin "6") (pinfunction "VCC(B)_6") (pintype "power_in"))
      (node (ref "IC4") (pin "1") (pinfunction "VDD_1") (pintype "bidirectional"))
      (node (ref "JP11") (pin "12") (pinfunction "12_12") (pintype "passive"))
      (node (ref "JP12") (pin "5") (pinfunction "5_5") (pintype "passive"))
      (node (ref "JP12") (pin "6") (pinfunction "6_6") (pintype "passive"))
      (node (ref "JP24") (pin "2") (pinfunction "2_2") (pintype "passive"))
      (node (ref "JP25") (pin "2") (pinfunction "2_2") (pintype "passive"))
      (node (ref "JP9") (pin "2") (pinfunction "2_2") (pintype "passive"))
      (node (ref "SV7") (pin "11") (pinfunction "11_11") (pintype "passive"))
    )
    (net (code "4") (name "5VREG*") (class "Default")
      (node (ref "Q1") (pin "3") (pinfunction "C_3") (pintype "bidirectional"))
      (node (ref "SV5") (pin "11") (pinfunction "11_11") (pintype "passive"))
    )
    (net (code "5") (name "5VREG_") (class "Default")
      (node (ref "JP10") (pin "5") (pinfunction "5_5") (pintype "passive"))
      (node (ref "R4") (pin "1") (pinfunction "1_1") (pintype "passive"))
    )
    (net (code "6") (name "A0") (class "Default")
      (node (ref "JP23") (pin "1") (pinfunction "1_1") (pintype "passive"))
      (node (ref "U7") (pin "4") (pinfunction "A_4") (pintype "passive"))
    )
    (net (code "7") (name "A0*") (class "Default")
      (node (ref "J6") (pin "1") (pinfunction "1_1") (pintype "passive"))
      (node (ref "JP21") (pin "1") (pinfunction "1_1") (pintype "passive"))
    )
    (net (code "8") (name "A0A") (class "Default")
      (node (ref "PTR1") (pin "1") (pinfunction "C_1") (pintype "passive"))
      (node (ref "R7") (pin "2") (pinfunction "2_2") (pintype "passive"))
      (node (ref "U1") (pin "3") (pinfunction "B0_3") (pintype "passive"))
    )
    (net (code "9") (name "A0B") (class "Default")
      (node (ref "Q3") (pin "C") (pinfunction "C1_C") (pintype "passive"))
      (node (ref "R29") (pin "2") (pinfunction "2_2") (pintype "passive"))
      (node (ref "U1") (pin "1") (pinfunction "B1_1") (pintype "passive"))
    )
    (net (code "10") (name "A0C") (class "Default")
      (node (ref "JP11") (pin "1") (pinfunction "1_1") (pintype "passive"))
      (node (ref "U7") (pin "3") (pinfunction "B0_3") (pintype "passive"))
    )
    (net (code "11") (name "A0D") (class "Default")
      (node (ref "JP12") (pin "2") (pinfunction "2_2") (pintype "passive"))
      (node (ref "U7") (pin "1") (pinfunction "B1_1") (pintype "passive"))
    )
    (net (code "12") (name "A0S") (class "Default")
      (node (ref "JP10") (pin "16") (pinfunction "16_16") (pintype "passive"))
      (node (ref "U1") (pin "4") (pinfunction "A_4") (pintype "passive"))
    )
    (net (code "13") (name "A1") (class "Default")
      (node (ref "JP23") (pin "3") (pinfunction "3_3") (pintype "passive"))
      (node (ref "U8") (pin "4") (pinfunction "A_4") (pintype "passive"))
    )
    (net (code "14") (name "A1*") (class "Default")
      (node (ref "J6") (pin "2") (pinfunction "2_2") (pintype "passive"))
      (node (ref "JP21") (pin "3") (pinfunction "3_3") (pintype "passive"))
    )
    (net (code "15") (name "A1A") (class "Default")
      (node (ref "PTR2") (pin "1") (pinfunction "C_1") (pintype "passive"))
      (node (ref "R9") (pin "2") (pinfunction "2_2") (pintype "passive"))
      (node (ref "U2") (pin "3") (pinfunction "B0_3") (pintype "passive"))
    )
    (net (code "16") (name "A1B") (class "Default")
      (node (ref "PTR3") (pin "1") (pinfunction "C_1") (pintype "passive"))
      (node (ref "R11") (pin "2") (pinfunction "2_2") (pintype "passive"))
      (node (ref "U2") (pin "1") (pinfunction "B1_1") (pintype "passive"))
    )
    (net (code "17") (name "A1C") (class "Default")
      (node (ref "JP11") (pin "2") (pinfunction "2_2") (pintype "passive"))
      (node (ref "U8") (pin "3") (pinfunction "B0_3") (pintype "passive"))
    )
    (net (code "18") (name "A1D") (class "Default")
      (node (ref "JP12") (pin "1") (pinfunction "1_1") (pintype "passive"))
      (node (ref "U8") (pin "1") (pinfunction "B1_1") (pintype "passive"))
    )
    (net (code "19") (name "A1S") (class "Default")
      (node (ref "JP10") (pin "15") (pinfunction "15_15") (pintype "passive"))
      (node (ref "U2") (pin "4") (pinfunction "A_4") (pintype "passive"))
    )
    (net (code "20") (name "A2") (class "Default")
      (node (ref "JP11") (pin "3") (pinfunction "3_3") (pintype "passive"))
      (node (ref "JP26") (pin "1") (pinfunction "1_1") (pintype "passive"))
    )
    (net (code "21") (name "A2*") (class "Default")
      (node (ref "J6") (pin "3") (pinfunction "3_3") (pintype "passive"))
      (node (ref "JP22") (pin "1") (pinfunction "1_1") (pintype "passive"))
    )
    (net (code "22") (name "A2A") (class "Default")
      (node (ref "PTR4") (pin "1") (pinfunction "C_1") (pintype "passive"))
      (node (ref "R13") (pin "2") (pinfunction "2_2") (pintype "passive"))
      (node (ref "U3") (pin "3") (pinfunction "B0_3") (pintype "passive"))
    )
    (net (code "23") (name "A2B") (class "Default")
      (node (ref "Q2") (pin "C") (pinfunction "C1_C") (pintype "passive"))
      (node (ref "R27") (pin "2") (pinfunction "2_2") (pintype "passive"))
      (node (ref "U3") (pin "1") (pinfunction "B1_1") (pintype "passive"))
    )
    (net (code "24") (name "A2S") (class "Default")
      (node (ref "JP10") (pin "14") (pinfunction "14_14") (pintype "passive"))
      (node (ref "U3") (pin "4") (pinfunction "A_4") (pintype "passive"))
    )
    (net (code "25") (name "A3") (class "Default")
      (node (ref "JP11") (pin "14") (pinfunction "14_14") (pintype "passive"))
      (node (ref "JP26") (pin "2") (pinfunction "2_2") (pintype "passive"))
    )
    (net (code "26") (name "A3*") (class "Default")
      (node (ref "J6") (pin "4") (pinfunction "4_4") (pintype "passive"))
      (node (ref "JP22") (pin "2") (pinfunction "2_2") (pintype "passive"))
    )
    (net (code "27") (name "A3A") (class "Default")
      (node (ref "PTR5") (pin "1") (pinfunction "C_1") (pintype "passive"))
      (node (ref "R15") (pin "2") (pinfunction "2_2") (pintype "passive"))
      (node (ref "U4") (pin "3") (pinfunction "B0_3") (pintype "passive"))
    )
    (net (code "28") (name "A3B") (class "Default")
      (node (ref "PTR6") (pin "1") (pinfunction "C_1") (pintype "passive"))
      (node (ref "R17") (pin "2") (pinfunction "2_2") (pintype "passive"))
      (node (ref "U4") (pin "1") (pinfunction "B1_1") (pintype "passive"))
    )
    (net (code "29") (name "A3S") (class "Default")
      (node (ref "JP10") (pin "3") (pinfunction "3_3") (pintype "passive"))
      (node (ref "U4") (pin "4") (pinfunction "A_4") (pintype "passive"))
    )
    (net (code "30") (name "A4") (class "Default")
      (node (ref "JP11") (pin "15") (pinfunction "15_15") (pintype "passive"))
      (node (ref "JP26") (pin "3") (pinfunction "3_3") (pintype "passive"))
    )
    (net (code "31") (name "A4*") (class "Default")
      (node (ref "J6") (pin "5") (pinfunction "5_5") (pintype "passive"))
      (node (ref "JP22") (pin "3") (pinfunction "3_3") (pintype "passive"))
    )
    (net (code "32") (name "A4A") (class "Default")
      (node (ref "PTR7") (pin "1") (pinfunction "C_1") (pintype "passive"))
      (node (ref "R19") (pin "2") (pinfunction "2_2") (pintype "passive"))
      (node (ref "U5") (pin "3") (pinfunction "B0_3") (pintype "passive"))
    )
    (net (code "33") (name "A4B") (class "Default")
      (node (ref "PTR8") (pin "1") (pinfunction "C_1") (pintype "passive"))
      (node (ref "R21") (pin "2") (pinfunction "2_2") (pintype "passive"))
      (node (ref "U5") (pin "1") (pinfunction "B1_1") (pintype "passive"))
    )
    (net (code "34") (name "A4S") (class "Default")
      (node (ref "JP10") (pin "2") (pinfunction "2_2") (pintype "passive"))
      (node (ref "U5") (pin "4") (pinfunction "A_4") (pintype "passive"))
    )
    (net (code "35") (name "A5") (class "Default")
      (node (ref "JP11") (pin "16") (pinfunction "16_16") (pintype "passive"))
      (node (ref "JP26") (pin "4") (pinfunction "4_4") (pintype "passive"))
    )
    (net (code "36") (name "A5*") (class "Default")
      (node (ref "J6") (pin "6") (pinfunction "6_6") (pintype "passive"))
      (node (ref "JP22") (pin "4") (pinfunction "4_4") (pintype "passive"))
    )
    (net (code "37") (name "A5A") (class "Default")
      (node (ref "PTR9") (pin "1") (pinfunction "C_1") (pintype "passive"))
      (node (ref "R23") (pin "2") (pinfunction "2_2") (pintype "passive"))
      (node (ref "U6") (pin "3") (pinfunction "B0_3") (pintype "passive"))
    )
    (net (code "38") (name "A5B") (class "Default")
      (node (ref "PTR10") (pin "1") (pinfunction "C_1") (pintype "passive"))
      (node (ref "R25") (pin "2") (pinfunction "2_2") (pintype "passive"))
      (node (ref "U6") (pin "1") (pinfunction "B1_1") (pintype "passive"))
    )
    (net (code "39") (name "A5S") (class "Default")
      (node (ref "JP10") (pin "1") (pinfunction "1_1") (pintype "passive"))
      (node (ref "U6") (pin "4") (pinfunction "A_4") (pintype "passive"))
    )
    (net (code "40") (name "D0") (class "Default")
      (node (ref "SV6") (pin "10") (pinfunction "10_10") (pintype "passive"))
      (node (ref "U$2") (pin "M0") (pinfunction "M0_M0") (pintype "bidirectional"))
    )
    (net (code "41") (name "D0*") (class "Default")
      (node (ref "J8") (pin "16") (pinfunction "16_16") (pintype "passive"))
      (node (ref "SV4") (pin "10") (pinfunction "10_10") (pintype "passive"))
    )
    (net (code "42") (name "D1") (class "Default")
      (node (ref "SV6") (pin "8") (pinfunction "8_8") (pintype "passive"))
      (node (ref "U$2") (pin "M1") (pinfunction "M1_M1") (pintype "bidirectional"))
    )
    (net (code "43") (name "D1*") (class "Default")
      (node (ref "J8") (pin "14") (pinfunction "14_14") (pintype "passive"))
      (node (ref "SV4") (pin "8") (pinfunction "8_8") (pintype "passive"))
    )
    (net (code "44") (name "D2") (class "Default")
      (node (ref "CONLEFT") (pin "M0") (pinfunction "M0_M0") (pintype "bidirectional"))
      (node (ref "SV6") (pin "2") (pinfunction "2_2") (pintype "passive"))
    )
    (net (code "45") (name "D2*") (class "Default")
      (node (ref "J8") (pin "12") (pinfunction "12_12") (pintype "passive"))
      (node (ref "SV4") (pin "2") (pinfunction "2_2") (pintype "passive"))
    )
    (net (code "46") (name "D3") (class "Default")
      (node (ref "JP25") (pin "3") (pinfunction "3_3") (pintype "passive"))
      (node (ref "SV6") (pin "6") (pinfunction "6_6") (pintype "passive"))
    )
    (net (code "47") (name "D3*") (class "Default")
      (node (ref "J8") (pin "10") (pinfunction "10_10") (pintype "passive"))
      (node (ref "SV4") (pin "6") (pinfunction "6_6") (pintype "passive"))
    )
    (net (code "48") (name "D4") (class "Default")
      (node (ref "CONLEFT") (pin "M1") (pinfunction "M1_M1") (pintype "bidirectional"))
      (node (ref "SV6") (pin "1") (pinfunction "1_1") (pintype "passive"))
    )
    (net (code "49") (name "D4*") (class "Default")
      (node (ref "J8") (pin "8") (pinfunction "8_8") (pintype "passive"))
      (node (ref "SV4") (pin "1") (pinfunction "1_1") (pintype "passive"))
    )
    (net (code "50") (name "D5") (class "Default")
      (node (ref "JP24") (pin "3") (pinfunction "3_3") (pintype "passive"))
      (node (ref "SV6") (pin "3") (pinfunction "3_3") (pintype "passive"))
    )
    (net (code "51") (name "D5*") (class "Default")
      (node (ref "J8") (pin "6") (pinfunction "6_6") (pintype "passive"))
      (node (ref "SV4") (pin "3") (pinfunction "3_3") (pintype "passive"))
    )
    (net (code "52") (name "D6") (class "Default")
      (node (ref "IC3") (pin "3") (pinfunction "A_3") (pintype "bidirectional"))
      (node (ref "JP13") (pin "1") (pinfunction "1_1") (pintype "passive"))
      (node (ref "SV6") (pin "5") (pinfunction "5_5") (pintype "passive"))
    )
    (net (code "53") (name "D6*") (class "Default")
      (node (ref "J8") (pin "4") (pinfunction "4_4") (pintype "passive"))
      (node (ref "SV4") (pin "5") (pinfunction "5_5") (pintype "passive"))
    )
    (net (code "54") (name "D7*") (class "Default")
      (node (ref "J8") (pin "2") (pinfunction "2_2") (pintype "passive"))
      (node (ref "R3") (pin "2") (pinfunction "2_2") (pintype "passive"))
    )
    (net (code "55") (name "D8") (class "Default")
      (node (ref "JP11") (pin "10") (pinfunction "10_10") (pintype "passive"))
      (node (ref "SV7") (pin "8") (pinfunction "8_8") (pintype "passive"))
    )
    (net (code "56") (name "D8*") (class "Default")
      (node (ref "SV5") (pin "8") (pinfunction "8_8") (pintype "passive"))
      (node (ref "U$1") (pin "1") (pinfunction "1_1") (pintype "passive"))
    )
    (net (code "57") (name "D8_") (class "Default")
      (node (ref "JP10") (pin "7") (pinfunction "7_7") (pintype "passive"))
      (node (ref "R6") (pin "2") (pinfunction "2_2") (pintype "passive"))
      (node (ref "U1") (pin "6") (pinfunction "S_6") (pintype "input"))
      (node (ref "U2") (pin "6") (pinfunction "S_6") (pintype "input"))
      (node (ref "U3") (pin "6") (pinfunction "S_6") (pintype "input"))
      (node (ref "U4") (pin "6") (pinfunction "S_6") (pintype "input"))
      (node (ref "U5") (pin "6") (pinfunction "S_6") (pintype "input"))
      (node (ref "U6") (pin "6") (pinfunction "S_6") (pintype "input"))
    )
    (net (code "58") (name "D9") (class "Default")
      (node (ref "JP11") (pin "7") (pinfunction "7_7") (pintype "passive"))
      (node (ref "SV7") (pin "6") (pinfunction "6_6") (pintype "passive"))
    )
    (net (code "59") (name "D9*") (class "Default")
      (node (ref "SV5") (pin "6") (pinfunction "6_6") (pintype "passive"))
      (node (ref "U$1") (pin "2") (pinfunction "2_2") (pintype "passive"))
    )
    (net (code "60") (name "D9_") (class "Default")
      (node (ref "JP10") (pin "10") (pinfunction "10_10") (pintype "passive"))
      (node (ref "JP15") (pin "1") (pinfunction "1_1") (pintype "passive"))
    )
    (net (code "61") (name "D10") (class "Default")
      (node (ref "SV7") (pin "4") (pinfunction "4_4") (pintype "passive"))
      (node (ref "U$2") (pin "DIR") (pinfunction "DIR_DIR") (pintype "bidirectional"))
    )
    (net (code "62") (name "D10*") (class "Default")
      (node (ref "SV5") (pin "4") (pinfunction "4_4") (pintype "passive"))
      (node (ref "U$1") (pin "3") (pinfunction "3_3") (pintype "passive"))
    )
    (net (code "63") (name "D11") (class "Default")
      (node (ref "SV7") (pin "2") (pinfunction "2_2") (pintype "passive"))
      (node (ref "U$2") (pin "STEP") (pinfunction "STEP_STEP") (pintype "bidirectional"))
    )
    (net (code "64") (name "D11*") (class "Default")
      (node (ref "SV5") (pin "2") (pinfunction "2_2") (pintype "passive"))
      (node (ref "U$1") (pin "4") (pinfunction "4_4") (pintype "passive"))
    )
    (net (code "65") (name "D12") (class "Default")
      (node (ref "CONLEFT") (pin "DIR") (pinfunction "DIR_DIR") (pintype "bidirectional"))
      (node (ref "SV7") (pin "1") (pinfunction "1_1") (pintype "passive"))
    )
    (net (code "66") (name "D12*") (class "Default")
      (node (ref "SV5") (pin "1") (pinfunction "1_1") (pintype "passive"))
      (node (ref "U$1") (pin "5") (pinfunction "5_5") (pintype "passive"))
    )
    (net (code "67") (name "D13") (class "Default")
      (node (ref "CONLEFT") (pin "STEP") (pinfunction "STEP_STEP") (pintype "bidirectional"))
      (node (ref "SV7") (pin "3") (pinfunction "3_3") (pintype "passive"))
    )
    (net (code "68") (name "D13*") (class "Default")
      (node (ref "SV5") (pin "3") (pinfunction "3_3") (pintype "passive"))
      (node (ref "U$1") (pin "6") (pinfunction "6_6") (pintype "passive"))
    )
    (net (code "69") (name "DP_") (class "Default")
      (node (ref "S6") (pin "2") (pinfunction "2_2") (pintype "bidirectional"))
    )
    (net (code "70") (name "GND") (class "Default")
      (node (ref "C1") (pin "2") (pinfunction "2_2") (pintype "passive"))
      (node (ref "C10") (pin "2") (pinfunction "2_2") (pintype "passive"))
      (node (ref "C11") (pin "2") (pinfunction "2_2") (pintype "passive"))
      (node (ref "C12") (pin "2") (pinfunction "2_2") (pintype "passive"))
      (node (ref "C13") (pin "2") (pinfunction "2_2") (pintype "passive"))
      (node (ref "C14") (pin "1") (pinfunction "1_1") (pintype "bidirectional"))
      (node (ref "C15") (pin "1") (pinfunction "1_1") (pintype "bidirectional"))
      (node (ref "C16") (pin "2") (pinfunction "2_2") (pintype "passive"))
      (node (ref "C17") (pin "1") (pinfunction "1_1") (pintype "passive"))
      (node (ref "C18") (pin "1") (pinfunction "1_1") (pintype "passive"))
      (node (ref "C19") (pin "1") (pinfunction "1_1") (pintype "passive"))
      (node (ref "C2") (pin "2") (pinfunction "2_2") (pintype "passive"))
      (node (ref "C20") (pin "1") (pinfunction "1_1") (pintype "passive"))
      (node (ref "C21") (pin "1") (pinfunction "1_1") (pintype "passive"))
      (node (ref "C22") (pin "1") (pinfunction "1_1") (pintype "passive"))
      (node (ref "C23") (pin "1") (pinfunction "1_1") (pintype "passive"))
      (node (ref "C24") (pin "1") (pinfunction "1_1") (pintype "passive"))
      (node (ref "C25") (pin "1") (pinfunction "1_1") (pintype "passive"))
      (node (ref "C26") (pin "1") (pinfunction "1_1") (pintype "passive"))
      (node (ref "C3") (pin "2") (pinfunction "2_2") (pintype "passive"))
      (node (ref "C4") (pin "2") (pinfunction "2_2") (pintype "passive"))
      (node (ref "C5") (pin "2") (pinfunction "2_2") (pintype "passive"))
      (node (ref "C6") (pin "2") (pinfunction "2_2") (pintype "passive"))
      (node (ref "C7") (pin "2") (pinfunction "2_2") (pintype "passive"))
      (node (ref "C8") (pin "2") (pinfunction "2_2") (pintype "passive"))
      (node (ref "C9") (pin "2") (pinfunction "2_2") (pintype "passive"))
      (node (ref "CONLEFT") (pin "GND0") (pinfunction "GND0_GND0") (pintype "bidirectional"))
      (node (ref "CONLEFT") (pin "GND1") (pinfunction "GND1_GND1") (pintype "bidirectional"))
      (node (ref "D1") (pin "C") (pinfunction "C_C") (pintype "passive"))
      (node (ref "D3") (pin "C") (pinfunction "C_C") (pintype "passive"))
      (node (ref "D5") (pin "C") (pinfunction "C_C") (pintype "passive"))
      (node (ref "D6") (pin "C") (pinfunction "C_C") (pintype "passive"))
      (node (ref "IC1") (pin "1") (pinfunction "GND_1") (pintype "input"))
      (node (ref "IC2") (pin "1") (pinfunction "GND_1") (pintype "input"))
      (node (ref "IC3") (pin "2") (pinfunction "GND_2") (pintype "power_in"))
      (node (ref "IC4") (pin "2") (pinfunction "VSS_2") (pintype "bidirectional"))
      (node (ref "IRLED0") (pin "2") (pinfunction "C_2") (pintype "passive"))
      (node (ref "IRLED1") (pin "2") (pinfunction "C_2") (pintype "passive"))
      (node (ref "IRLED10") (pin "2") (pinfunction "C_2") (pintype "passive"))
      (node (ref "IRLED2") (pin "2") (pinfunction "C_2") (pintype "passive"))
      (node (ref "IRLED3") (pin "2") (pinfunction "C_2") (pintype "passive"))
      (node (ref "IRLED4") (pin "2") (pinfunction "C_2") (pintype "passive"))
      (node (ref "IRLED5") (pin "2") (pinfunction "C_2") (pintype "passive"))
      (node (ref "IRLED6") (pin "2") (pinfunction "C_2") (pintype "passive"))
      (node (ref "IRLED7") (pin "2") (pinfunction "C_2") (pintype "passive"))
      (node (ref "IRLED8") (pin "2") (pinfunction "C_2") (pintype "passive"))
      (node (ref "IRLED9") (pin "2") (pinfunction "C_2") (pintype "passive"))
      (node (ref "J3") (pin "1") (pinfunction "1_1") (pintype "passive"))
      (node (ref "J5") (pin "6") (pinfunction "6_6") (pintype "passive"))
      (node (ref "J5") (pin "7") (pinfunction "7_7") (pintype "passive"))
      (node (ref "JP10") (pin "11") (pinfunction "11_11") (pintype "passive"))
      (node (ref "JP10") (pin "6") (pinfunction "6_6") (pintype "passive"))
      (node (ref "JP11") (pin "11") (pinfunction "11_11") (pintype "passive"))
      (node (ref "JP11") (pin "6") (pinfunction "6_6") (pintype "passive"))
      (node (ref "JP12") (pin "7") (pinfunction "7_7") (pintype "passive"))
      (node (ref "JP12") (pin "8") (pinfunction "8_8") (pintype "passive"))
      (node (ref "JP21") (pin "2") (pinfunction "2_2") (pintype "passive"))
      (node (ref "JP23") (pin "2") (pinfunction "2_2") (pintype "passive"))
      (node (ref "JP24") (pin "1") (pinfunction "1_1") (pintype "passive"))
      (node (ref "JP25") (pin "1") (pinfunction "1_1") (pintype "passive"))
      (node (ref "LED1") (pin "4") (pinfunction "GND_4") (pintype "power_in"))
      (node (ref "LED2") (pin "4") (pinfunction "GND_4") (pintype "power_in"))
      (node (ref "LED3") (pin "4") (pinfunction "GND_4") (pintype "power_in"))
      (node (ref "LED4") (pin "4") (pinfunction "GND_4") (pintype "power_in"))
      (node (ref "LED5") (pin "4") (pinfunction "GND_4") (pintype "power_in"))
      (node (ref "LED6") (pin "4") (pinfunction "GND_4") (pintype "power_in"))
      (node (ref "LED7") (pin "4") (pinfunction "GND_4") (pintype "power_in"))
      (node (ref "LED8") (pin "4") (pinfunction "GND_4") (pintype "power_in"))
      (node (ref "LED9") (pin "4") (pinfunction "GND_4") (pintype "power_in"))
      (node (ref "LS1") (pin "-") (pinfunction "2_-") (pintype "passive"))
      (node (ref "PTR1") (pin "2") (pinfunction "E_2") (pintype "passive"))
      (node (ref "PTR10") (pin "2") (pinfunction "E_2") (pintype "passive"))
      (node (ref "PTR2") (pin "2") (pinfunction "E_2") (pintype "passive"))
      (node (ref "PTR3") (pin "2") (pinfunction "E_2") (pintype "passive"))
      (node (ref "PTR4") (pin "2") (pinfunction "E_2") (pintype "passive"))
      (node (ref "PTR5") (pin "2") (pinfunction "E_2") (pintype "passive"))
      (node (ref "PTR6") (pin "2") (pinfunction "E_2") (pintype "passive"))
      (node (ref "PTR7") (pin "2") (pinfunction "E_2") (pintype "passive"))
      (node (ref "PTR8") (pin "2") (pinfunction "E_2") (pintype "passive"))
      (node (ref "PTR9") (pin "2") (pinfunction "E_2") (pintype "passive"))
      (node (ref "Q2") (pin "E") (pinfunction "E1_E") (pintype "passive"))
      (node (ref "Q3") (pin "E") (pinfunction "E1_E") (pintype "passive"))
      (node (ref "R32") (pin "1") (pinfunction "1_1") (pintype "passive"))
      (node (ref "R5") (pin "2") (pinfunction "2_2") (pintype "passive"))
      (node (ref "R6") (pin "1") (pinfunction "1_1") (pintype "passive"))
      (node (ref "S2") (pin "5") (pinfunction "COMMON_5") (pintype "bidirectional"))
      (node (ref "SV3") (pin "1") (pinfunction "1_1") (pintype "passive"))
      (node (ref "SV5") (pin "12") (pinfunction "12_12") (pintype "passive"))
      (node (ref "SV5") (pin "9") (pinfunction "9_9") (pintype "passive"))
      (node (ref "SV7") (pin "12") (pinfunction "12_12") (pintype "passive"))
      (node (ref "SV7") (pin "9") (pinfunction "9_9") (pintype "passive"))
      (node (ref "U$1") (pin "7") (pinfunction "7_7") (pintype "passive"))
      (node (ref "U$2") (pin "GND0") (pinfunction "GND0_GND0") (pintype "bidirectional"))
      (node (ref "U$2") (pin "GND1") (pinfunction "GND1_GND1") (pintype "bidirectional"))
      (node (ref "U1") (pin "2") (pinfunction "GND_2") (pintype "passive"))
      (node (ref "U2") (pin "2") (pinfunction "GND_2") (pintype "passive"))
      (node (ref "U3") (pin "2") (pinfunction "GND_2") (pintype "passive"))
      (node (ref "U4") (pin "2") (pinfunction "GND_2") (pintype "passive"))
      (node (ref "U5") (pin "2") (pinfunction "GND_2") (pintype "passive"))
      (node (ref "U6") (pin "2") (pinfunction "GND_2") (pintype "passive"))
      (node (ref "U7") (pin "2") (pinfunction "GND_2") (pintype "passive"))
      (node (ref "U8") (pin "2") (pinfunction "GND_2") (pintype "passive"))
    )
    (net (code "71") (name "Net-(CONLEFT-PadA1)") (class "Default")
      (node (ref "CONLEFT") (pin "A1") (pinfunction "A1_A1") (pintype "bidirectional"))
      (node (ref "SV2") (pin "3") (pinfunction "3_3") (pintype "passive"))
    )
    (net (code "72") (name "Net-(CONLEFT-PadA2)") (class "Default")
      (node (ref "CONLEFT") (pin "A2") (pinfunction "A2_A2") (pintype "bidirectional"))
      (node (ref "SV2") (pin "4") (pinfunction "4_4") (pintype "passive"))
    )
    (net (code "73") (name "Net-(CONLEFT-PadB1)") (class "Default")
      (node (ref "CONLEFT") (pin "B1") (pinfunction "B1_B1") (pintype "bidirectional"))
      (node (ref "SV2") (pin "2") (pinfunction "2_2") (pintype "passive"))
    )
    (net (code "74") (name "Net-(CONLEFT-PadB2)") (class "Default")
      (node (ref "CONLEFT") (pin "B2") (pinfunction "B2_B2") (pintype "bidirectional"))
      (node (ref "SV2") (pin "1") (pinfunction "1_1") (pintype "passive"))
    )
    (net (code "75") (name "Net-(D1-PadA)") (class "Default")
      (node (ref "D1") (pin "A") (pinfunction "A_A") (pintype "passive"))
      (node (ref "R1") (pin "2") (pinfunction "2_2") (pintype "passive"))
    )
    (net (code "76") (name "Net-(D3-PadA)") (class "Default")
      (node (ref "D3") (pin "A") (pinfunction "A_A") (pintype "passive"))
      (node (ref "R4") (pin "2") (pinfunction "2_2") (pintype "passive"))
    )
    (net (code "77") (name "Net-(D4-PadA)") (class "Default")
      (node (ref "D4") (pin "A") (pinfunction "A_A") (pintype "passive"))
      (node (ref "S3") (pin "3") (pinfunction "3_3") (pintype "bidirectional"))
      (node (ref "SJ1") (pin "1") (pinfunction "1_1") (pintype "passive"))
    )
    (net (code "78") (name "Net-(D5-PadA)") (class "Default")
      (node (ref "D5") (pin "A") (pinfunction "A_A") (pintype "passive"))
      (node (ref "R30") (pin "2") (pinfunction "2_2") (pintype "passive"))
    )
    (net (code "79") (name "Net-(D6-PadA)") (class "Default")
      (node (ref "D6") (pin "A") (pinfunction "A_A") (pintype "passive"))
      (node (ref "R28") (pin "2") (pinfunction "2_2") (pintype "passive"))
    )
    (net (code "80") (name "Net-(D7-PadC)") (class "Default")
      (node (ref "D7") (pin "C") (pinfunction "C_C") (pintype "passive"))
      (node (ref "JP23") (pin "4") (pinfunction "4_4") (pintype "passive"))
    )
    (net (code "81") (name "Net-(IC3-B)") (class "Default")
      (node (ref "IC3") (pin "4") (pinfunction "B_4") (pintype "bidirectional"))
      (node (ref "JP1") (pin "1") (pinfunction "1_1") (pintype "passive"))
      (node (ref "JP13") (pin "2") (pinfunction "2_2") (pintype "passive"))
      (node (ref "LED1") (pin "1") (pinfunction "DI_1") (pintype "input"))
    )
    (net (code "82") (name "Net-(IC4-AIN)") (class "Default")
      (node (ref "IC4") (pin "3") (pinfunction "AIN_3") (pintype "bidirectional"))
      (node (ref "R2") (pin "2") (pinfunction "2_2") (pintype "passive"))
      (node (ref "R5") (pin "1") (pinfunction "1_1") (pintype "passive"))
    )
    (net (code "83") (name "Net-(IRLED0-A)") (class "Default")
      (node (ref "IRLED0") (pin "1") (pinfunction "A_1") (pintype "passive"))
      (node (ref "R31") (pin "2") (pinfunction "2_2") (pintype "passive"))
    )
    (net (code "84") (name "Net-(IRLED1-A)") (class "Default")
      (node (ref "IRLED1") (pin "1") (pinfunction "A_1") (pintype "passive"))
      (node (ref "R8") (pin "2") (pinfunction "2_2") (pintype "passive"))
    )
    (net (code "85") (name "Net-(IRLED2-A)") (class "Default")
      (node (ref "IRLED2") (pin "1") (pinfunction "A_1") (pintype "passive"))
      (node (ref "R10") (pin "2") (pinfunction "2_2") (pintype "passive"))
    )
    (net (code "86") (name "Net-(IRLED3-A)") (class "Default")
      (node (ref "IRLED3") (pin "1") (pinfunction "A_1") (pintype "passive"))
      (node (ref "R12") (pin "2") (pinfunction "2_2") (pintype "passive"))
    )
    (net (code "87") (name "Net-(IRLED4-A)") (class "Default")
      (node (ref "IRLED4") (pin "1") (pinfunction "A_1") (pintype "passive"))
      (node (ref "R14") (pin "2") (pinfunction "2_2") (pintype "passive"))
    )
    (net (code "88") (name "Net-(IRLED5-A)") (class "Default")
      (node (ref "IRLED5") (pin "1") (pinfunction "A_1") (pintype "passive"))
      (node (ref "R16") (pin "2") (pinfunction "2_2") (pintype "passive"))
    )
    (net (code "89") (name "Net-(IRLED6-A)") (class "Default")
      (node (ref "IRLED6") (pin "1") (pinfunction "A_1") (pintype "passive"))
      (node (ref "R18") (pin "2") (pinfunction "2_2") (pintype "passive"))
    )
    (net (code "90") (name "Net-(IRLED7-A)") (class "Default")
      (node (ref "IRLED7") (pin "1") (pinfunction "A_1") (pintype "passive"))
      (node (ref "R20") (pin "2") (pinfunction "2_2") (pintype "passive"))
    )
    (net (code "91") (name "Net-(IRLED8-A)") (class "Default")
      (node (ref "IRLED8") (pin "1") (pinfunction "A_1") (pintype "passive"))
      (node (ref "R22") (pin "2") (pinfunction "2_2") (pintype "passive"))
    )
    (net (code "92") (name "Net-(IRLED9-A)") (class "Default")
      (node (ref "IRLED9") (pin "1") (pinfunction "A_1") (pintype "passive"))
      (node (ref "R24") (pin "2") (pinfunction "2_2") (pintype "passive"))
    )
    (net (code "93") (name "Net-(IRLED10-A)") (class "Default")
      (node (ref "IRLED10") (pin "1") (pinfunction "A_1") (pintype "passive"))
      (node (ref "R26") (pin "2") (pinfunction "2_2") (pintype "passive"))
    )
    (net (code "94") (name "Net-(J3-Pad2)") (class "Default")
      (node (ref "J3") (pin "2") (pinfunction "2_2") (pintype "passive"))
      (node (ref "S3") (pin "2") (pinfunction "2_2") (pintype "bidirectional"))
    )
    (net (code "95") (name "Net-(JP14-Pad1)") (class "Default")
      (node (ref "JP14") (pin "1") (pinfunction "1_1") (pintype "passive"))
      (node (ref "JP15") (pin "2") (pinfunction "2_2") (pintype "passive"))
      (node (ref "S5") (pin "2") (pinfunction "2_2") (pintype "bidirectional"))
    )
    (net (code "96") (name "Net-(JP14-Pad2)") (class "Default")
      (node (ref "JP14") (pin "2") (pinfunction "2_2") (pintype "passive"))
      (node (ref "S6") (pin "1") (pinfunction "1_1") (pintype "bidirectional"))
    )
    (net (code "97") (name "Net-(LED1-DO)") (class "Default")
      (node (ref "JP1") (pin "2") (pinfunction "2_2") (pintype "passive"))
      (node (ref "JP2") (pin "1") (pinfunction "1_1") (pintype "passive"))
      (node (ref "LED1") (pin "3") (pinfunction "DO_3") (pintype "output"))
      (node (ref "LED2") (pin "1") (pinfunction "DI_1") (pintype "input"))
    )
    (net (code "98") (name "Net-(LED1-VDD)") (class "Default")
      (node (ref "C1") (pin "1") (pinfunction "1_1") (pintype "passive"))
      (node (ref "C2") (pin "1") (pinfunction "1_1") (pintype "passive"))
      (node (ref "C3") (pin "1") (pinfunction "1_1") (pintype "passive"))
      (node (ref "C4") (pin "1") (pinfunction "1_1") (pintype "passive"))
      (node (ref "C5") (pin "1") (pinfunction "1_1") (pintype "passive"))
      (node (ref "C6") (pin "1") (pinfunction "1_1") (pintype "passive"))
      (node (ref "C7") (pin "1") (pinfunction "1_1") (pintype "passive"))
      (node (ref "C8") (pin "1") (pinfunction "1_1") (pintype "passive"))
      (node (ref "C9") (pin "1") (pinfunction "1_1") (pintype "passive"))
      (node (ref "JP9") (pin "1") (pinfunction "1_1") (pintype "passive"))
      (node (ref "LED1") (pin "2") (pinfunction "VDD_2") (pintype "power_in"))
      (node (ref "LED2") (pin "2") (pinfunction "VDD_2") (pintype "power_in"))
      (node (ref "LED3") (pin "2") (pinfunction "VDD_2") (pintype "power_in"))
      (node (ref "LED4") (pin "2") (pinfunction "VDD_2") (pintype "power_in"))
      (node (ref "LED5") (pin "2") (pinfunction "VDD_2") (pintype "power_in"))
      (node (ref "LED6") (pin "2") (pinfunction "VDD_2") (pintype "power_in"))
      (node (ref "LED7") (pin "2") (pinfunction "VDD_2") (pintype "power_in"))
      (node (ref "LED8") (pin "2") (pinfunction "VDD_2") (pintype "power_in"))
      (node (ref "LED9") (pin "2") (pinfunction "VDD_2") (pintype "power_in"))
    )
    (net (code "99") (name "Net-(LED2-DO)") (class "Default")
      (node (ref "JP2") (pin "2") (pinfunction "2_2") (pintype "passive"))
      (node (ref "JP3") (pin "1") (pinfunction "1_1") (pintype "passive"))
      (node (ref "LED2") (pin "3") (pinfunction "DO_3") (pintype "output"))
      (node (ref "LED3") (pin "1") (pinfunction "DI_1") (pintype "input"))
    )
    (net (code "100") (name "Net-(LED3-DO)") (class "Default")
      (node (ref "JP3") (pin "2") (pinfunction "2_2") (pintype "passive"))
      (node (ref "JP4") (pin "1") (pinfunction "1_1") (pintype "passive"))
      (node (ref "LED3") (pin "3") (pinfunction "DO_3") (pintype "output"))
      (node (ref "LED4") (pin "1") (pinfunction "DI_1") (pintype "input"))
    )
    (net (code "101") (name "Net-(LED4-DO)") (class "Default")
      (node (ref "JP4") (pin "2") (pinfunction "2_2") (pintype "passive"))
      (node (ref "JP5") (pin "1") (pinfunction "1_1") (pintype "passive"))
      (node (ref "LED4") (pin "3") (pinfunction "DO_3") (pintype "output"))
      (node (ref "LED5") (pin "1") (pinfunction "DI_1") (pintype "input"))
    )
    (net (code "102") (name "Net-(LED5-DO)") (class "Default")
      (node (ref "JP5") (pin "2") (pinfunction "2_2") (pintype "passive"))
      (node (ref "JP6") (pin "1") (pinfunction "1_1") (pintype "passive"))
      (node (ref "LED5") (pin "3") (pinfunction "DO_3") (pintype "output"))
      (node (ref "LED6") (pin "1") (pinfunction "DI_1") (pintype "input"))
    )
    (net (code "103") (name "Net-(LED6-DO)") (class "Default")
      (node (ref "JP6") (pin "2") (pinfunction "2_2") (pintype "passive"))
      (node (ref "JP7") (pin "1") (pinfunction "1_1") (pintype "passive"))
      (node (ref "LED6") (pin "3") (pinfunction "DO_3") (pintype "output"))
      (node (ref "LED7") (pin "1") (pinfunction "DI_1") (pintype "input"))
    )
    (net (code "104") (name "Net-(LED7-DO)") (class "Default")
      (node (ref "JP7") (pin "2") (pinfunction "2_2") (pintype "passive"))
      (node (ref "JP8") (pin "1") (pinfunction "1_1") (pintype "passive"))
      (node (ref "LED7") (pin "3") (pinfunction "DO_3") (pintype "output"))
      (node (ref "LED8") (pin "1") (pinfunction "DI_1") (pintype "input"))
    )
    (net (code "105") (name "Net-(LED8-DO)") (class "Default")
      (node (ref "JP8") (pin "2") (pinfunction "2_2") (pintype "passive"))
      (node (ref "LED8") (pin "3") (pinfunction "DO_3") (pintype "output"))
      (node (ref "LED9") (pin "1") (pinfunction "DI_1") (pintype "input"))
    )
    (net (code "106") (name "Net-(LS1-1)") (class "Default")
      (node (ref "LS1") (pin "+") (pinfunction "1_+") (pintype "passive"))
      (node (ref "Q1") (pin "2") (pinfunction "E_2") (pintype "bidirectional"))
    )
    (net (code "107") (name "Net-(Q1-B)") (class "Default")
      (node (ref "Q1") (pin "1") (pinfunction "B_1") (pintype "bidirectional"))
      (node (ref "R3") (pin "1") (pinfunction "1_1") (pintype "passive"))
    )
    (net (code "108") (name "Net-(SV1-Pad1)") (class "Default")
      (node (ref "SV1") (pin "1") (pinfunction "1_1") (pintype "passive"))
      (node (ref "U$2") (pin "B2") (pinfunction "B2_B2") (pintype "bidirectional"))
    )
    (net (code "109") (name "Net-(SV1-Pad2)") (class "Default")
      (node (ref "SV1") (pin "2") (pinfunction "2_2") (pintype "passive"))
      (node (ref "U$2") (pin "B1") (pinfunction "B1_B1") (pintype "bidirectional"))
    )
    (net (code "110") (name "Net-(SV1-Pad3)") (class "Default")
      (node (ref "SV1") (pin "3") (pinfunction "3_3") (pintype "passive"))
      (node (ref "U$2") (pin "A1") (pinfunction "A1_A1") (pintype "bidirectional"))
    )
    (net (code "111") (name "Net-(SV1-Pad4)") (class "Default")
      (node (ref "SV1") (pin "4") (pinfunction "4_4") (pintype "passive"))
      (node (ref "U$2") (pin "A2") (pinfunction "A2_A2") (pintype "bidirectional"))
    )
    (net (code "112") (name "PTB18*") (class "Default")
      (node (ref "J8") (pin "15") (pinfunction "15_15") (pintype "passive"))
      (node (ref "S2") (pin "4") (pinfunction "B_4") (pintype "bidirectional"))
    )
    (net (code "113") (name "PTB19*") (class "Default")
      (node (ref "J8") (pin "13") (pinfunction "13_13") (pintype "passive"))
      (node (ref "S2") (pin "6") (pinfunction "D_6") (pintype "bidirectional"))
    )
    (net (code "114") (name "PTC0*") (class "Default")
      (node (ref "J8") (pin "5") (pinfunction "5_5") (pintype "passive"))
      (node (ref "S2") (pin "1") (pinfunction "A_1") (pintype "bidirectional"))
    )
    (net (code "115") (name "PTC1") (class "Default")
      (node (ref "R32") (pin "2") (pinfunction "2_2") (pintype "passive"))
      (node (ref "SV6") (pin "4") (pinfunction "4_4") (pintype "passive"))
      (node (ref "U7") (pin "6") (pinfunction "S_6") (pintype "input"))
      (node (ref "U8") (pin "6") (pinfunction "S_6") (pintype "input"))
    )
    (net (code "116") (name "PTC1*") (class "Default")
      (node (ref "J8") (pin "11") (pinfunction "11_11") (pintype "passive"))
      (node (ref "SV4") (pin "4") (pinfunction "4_4") (pintype "passive"))
    )
    (net (code "117") (name "PTC5") (class "Default")
      (node (ref "SV6") (pin "9") (pinfunction "9_9") (pintype "passive"))
      (node (ref "U$2") (pin "EN") (pinfunction "EN_EN") (pintype "bidirectional"))
    )
    (net (code "118") (name "PTC5*") (class "Default")
      (node (ref "J8") (pin "1") (pinfunction "1_1") (pintype "passive"))
      (node (ref "SV4") (pin "9") (pinfunction "9_9") (pintype "passive"))
    )
    (net (code "119") (name "PTC7") (class "Default")
      (node (ref "CONLEFT") (pin "EN") (pinfunction "EN_EN") (pintype "bidirectional"))
      (node (ref "SV6") (pin "7") (pinfunction "7_7") (pintype "passive"))
    )
    (net (code "120") (name "PTC7*") (class "Default")
      (node (ref "J8") (pin "3") (pinfunction "3_3") (pintype "passive"))
      (node (ref "SV4") (pin "7") (pinfunction "7_7") (pintype "passive"))
    )
    (net (code "121") (name "PTC8*") (class "Default")
      (node (ref "J8") (pin "9") (pinfunction "9_9") (pintype "passive"))
      (node (ref "S2") (pin "3") (pinfunction "C_3") (pintype "bidirectional"))
    )
    (net (code "122") (name "PTC9*") (class "Default")
      (node (ref "J8") (pin "7") (pinfunction "7_7") (pintype "passive"))
      (node (ref "S2") (pin "2") (pinfunction "CENTER_2") (pintype "bidirectional"))
    )
    (net (code "123") (name "PTE26") (class "Default")
      (node (ref "J1") (pin "1") (pinfunction "1_1") (pintype "passive"))
      (node (ref "SV7") (pin "10") (pinfunction "10_10") (pintype "passive"))
    )
    (net (code "124") (name "PTE26*") (class "Default")
      (node (ref "J7") (pin "1") (pinfunction "1_1") (pintype "passive"))
      (node (ref "SV5") (pin "10") (pinfunction "10_10") (pintype "passive"))
    )
    (net (code "125") (name "SCL") (class "Default")
      (node (ref "IC4") (pin "5") (pinfunction "SCL_5") (pintype "bidirectional"))
      (node (ref "JP11") (pin "9") (pinfunction "9_9") (pintype "passive"))
      (node (ref "JP27") (pin "2") (pinfunction "2_2") (pintype "passive"))
      (node (ref "SV3") (pin "3") (pinfunction "3_3") (pintype "passive"))
      (node (ref "SV7") (pin "7") (pinfunction "7_7") (pintype "passive"))
    )
    (net (code "126") (name "SCL*") (class "Default")
      (node (ref "SV5") (pin "7") (pinfunction "7_7") (pintype "passive"))
      (node (ref "U$1") (pin "10") (pinfunction "10_10") (pintype "passive"))
    )
    (net (code "127") (name "SCL_") (class "Default")
      (node (ref "JP10") (pin "8") (pinfunction "8_8") (pintype "passive"))
    )
    (net (code "128") (name "SDA") (class "Default")
      (node (ref "IC4") (pin "4") (pinfunction "SDA_4") (pintype "bidirectional"))
      (node (ref "JP11") (pin "8") (pinfunction "8_8") (pintype "passive"))
      (node (ref "JP27") (pin "1") (pinfunction "1_1") (pintype "passive"))
      (node (ref "SV3") (pin "4") (pinfunction "4_4") (pintype "passive"))
      (node (ref "SV7") (pin "5") (pinfunction "5_5") (pintype "passive"))
    )
    (net (code "129") (name "SDA*") (class "Default")
      (node (ref "SV5") (pin "5") (pinfunction "5_5") (pintype "passive"))
      (node (ref "U$1") (pin "9") (pinfunction "9_9") (pintype "passive"))
    )
    (net (code "130") (name "SDA_") (class "Default")
      (node (ref "JP10") (pin "9") (pinfunction "9_9") (pintype "passive"))
    )
    (net (code "131") (name "VIN") (class "Default")
      (node (ref "C10") (pin "1") (pinfunction "1_1") (pintype "passive"))
      (node (ref "C12") (pin "1") (pinfunction "1_1") (pintype "passive"))
      (node (ref "C14") (pin "2") (pinfunction "2_2") (pintype "bidirectional"))
      (node (ref "C15") (pin "2") (pinfunction "2_2") (pintype "bidirectional"))
      (node (ref "CONLEFT") (pin "VMOT") (pinfunction "VMOT_VMOT") (pintype "bidirectional"))
      (node (ref "D4") (pin "C") (pinfunction "C_C") (pintype "passive"))
      (node (ref "D7") (pin "A") (pinfunction "A_A") (pintype "passive"))
      (node (ref "IC1") (pin "3") (pinfunction "IN_3") (pintype "input"))
      (node (ref "IC2") (pin "3") (pinfunction "IN_3") (pintype "input"))
      (node (ref "JP11") (pin "4") (pinfunction "4_4") (pintype "passive"))
      (node (ref "R1") (pin "1") (pinfunction "1_1") (pintype "passive"))
      (node (ref "R2") (pin "1") (pinfunction "1_1") (pintype "passive"))
      (node (ref "SJ1") (pin "2") (pinfunction "2_2") (pintype "passive"))
      (node (ref "U$2") (pin "VMOT") (pinfunction "VMOT_VMOT") (pintype "bidirectional"))
    )
    (net (code "132") (name "VIN*") (class "Default")
      (node (ref "J5") (pin "8") (pinfunction "8_8") (pintype "passive"))
      (node (ref "JP21") (pin "4") (pinfunction "4_4") (pintype "passive"))
    )
    (net (code "133") (name "VIN_") (class "Default")
      (node (ref "JP10") (pin "13") (pinfunction "13_13") (pintype "passive"))
    )
    (net (code "134") (name "unconnected-(CONLEFT-(CONFIG)-PadCONFIG)") (class "Default")
      (node (ref "CONLEFT") (pin "CONFIG") (pinfunction "(CONFIG)_CONFIG") (pintype "bidirectional"))
    )
    (net (code "135") (name "unconnected-(CONLEFT-(VREF)-PadVREF)") (class "Default")
      (node (ref "CONLEFT") (pin "VREF") (pinfunction "(VREF)_VREF") (pintype "bidirectional"))
    )
    (net (code "136") (name "unconnected-(CONLEFT-PadFLT)") (class "Default")
      (node (ref "CONLEFT") (pin "FLT") (pinfunction "FLT_FLT") (pintype "bidirectional"))
    )
    (net (code "137") (name "unconnected-(J5-Pad1)") (class "Default")
      (node (ref "J5") (pin "1") (pinfunction "1_1") (pintype "passive"))
    )
    (net (code "138") (name "unconnected-(J5-Pad2)") (class "Default")
      (node (ref "J5") (pin "2") (pinfunction "2_2") (pintype "passive"))
    )
    (net (code "139") (name "unconnected-(J5-Pad3)") (class "Default")
      (node (ref "J5") (pin "3") (pinfunction "3_3") (pintype "passive"))
    )
    (net (code "140") (name "unconnected-(J5-Pad4)") (class "Default")
      (node (ref "J5") (pin "4") (pinfunction "4_4") (pintype "passive"))
    )
    (net (code "141") (name "unconnected-(J5-Pad5)") (class "Default")
      (node (ref "J5") (pin "5") (pinfunction "5_5") (pintype "passive"))
    )
    (net (code "142") (name "unconnected-(JP10-Pad12)") (class "Default")
      (node (ref "JP10") (pin "12") (pinfunction "12_12") (pintype "passive"))
    )
    (net (code "143") (name "unconnected-(JP11-Pad5)") (class "Default")
      (node (ref "JP11") (pin "5") (pinfunction "5_5") (pintype "passive"))
    )
    (net (code "144") (name "unconnected-(LED9-DO-Pad3)") (class "Default")
      (node (ref "LED9") (pin "3") (pinfunction "DO_3") (pintype "output"))
    )
    (net (code "145") (name "unconnected-(S2-Pad7)") (class "Default")
      (node (ref "S2") (pin "7") (pinfunction "7_7") (pintype "bidirectional"))
    )
    (net (code "146") (name "unconnected-(S2-Pad8)") (class "Default")
      (node (ref "S2") (pin "8") (pinfunction "8_8") (pintype "bidirectional"))
    )
    (net (code "147") (name "unconnected-(S3-Pad1)") (class "Default")
      (node (ref "S3") (pin "1") (pinfunction "1_1") (pintype "bidirectional"))
    )
    (net (code "148") (name "unconnected-(S5-Pad3)") (class "Default")
      (node (ref "S5") (pin "3") (pinfunction "3_3") (pintype "bidirectional"))
    )
    (net (code "149") (name "unconnected-(S6-Pad3)") (class "Default")
      (node (ref "S6") (pin "3") (pinfunction "3_3") (pintype "bidirectional"))
    )
    (net (code "150") (name "unconnected-(U$1-Pad8)") (class "Default")
      (node (ref "U$1") (pin "8") (pinfunction "8_8") (pintype "passive"))
    )
    (net (code "151") (name "unconnected-(U$2-(CONFIG)-PadCONFIG)") (class "Default")
      (node (ref "U$2") (pin "CONFIG") (pinfunction "(CONFIG)_CONFIG") (pintype "bidirectional"))
    )
    (net (code "152") (name "unconnected-(U$2-(VREF)-PadVREF)") (class "Default")
      (node (ref "U$2") (pin "VREF") (pinfunction "(VREF)_VREF") (pintype "bidirectional"))
    )
    (net (code "153") (name "unconnected-(U$2-PadFLT)") (class "Default")
      (node (ref "U$2") (pin "FLT") (pinfunction "FLT_FLT") (pintype "bidirectional"))
    )
  )
)
